# app1.net
KiCad netlist of a schematic drawn in EAGLE
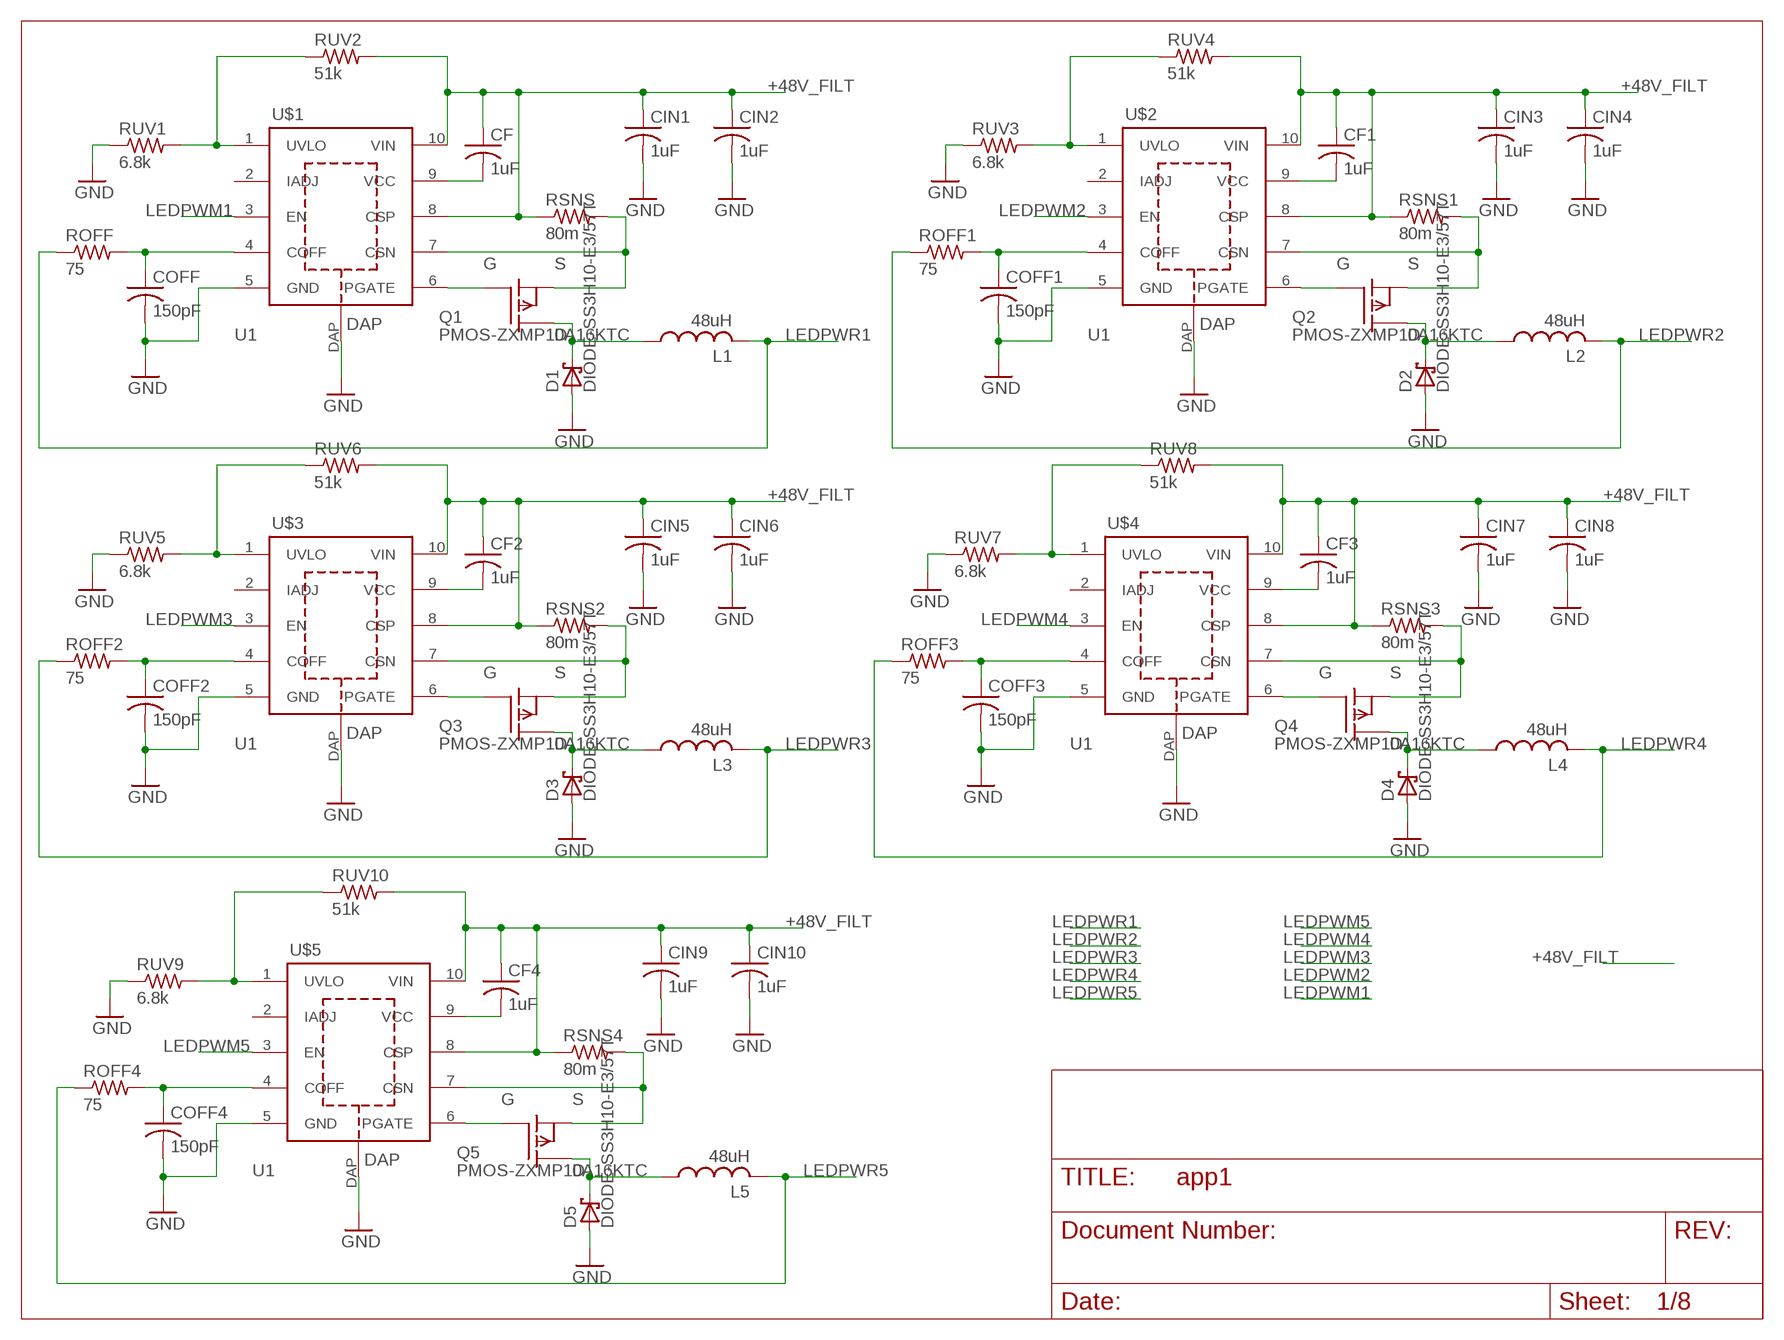
[diagram p0: schematic, sheet 1]
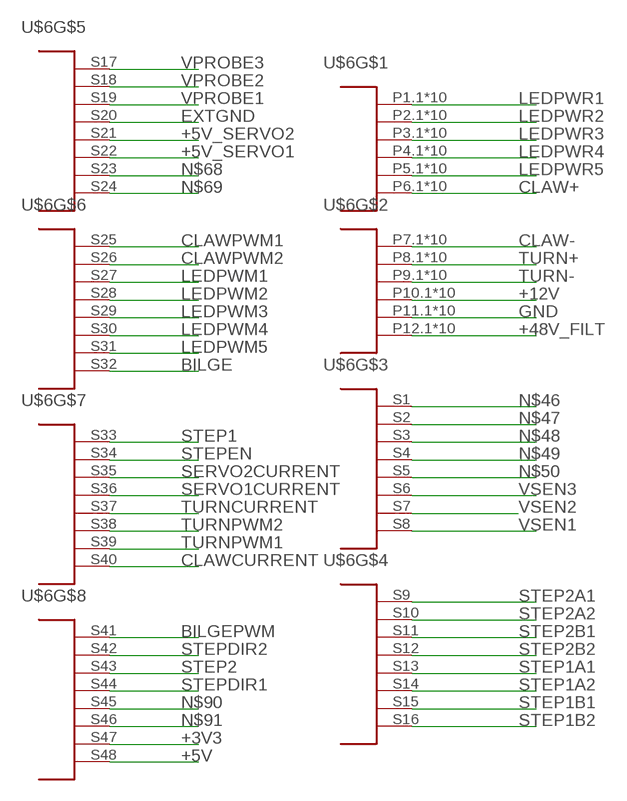
[diagram p1: schematic, sheet 2]
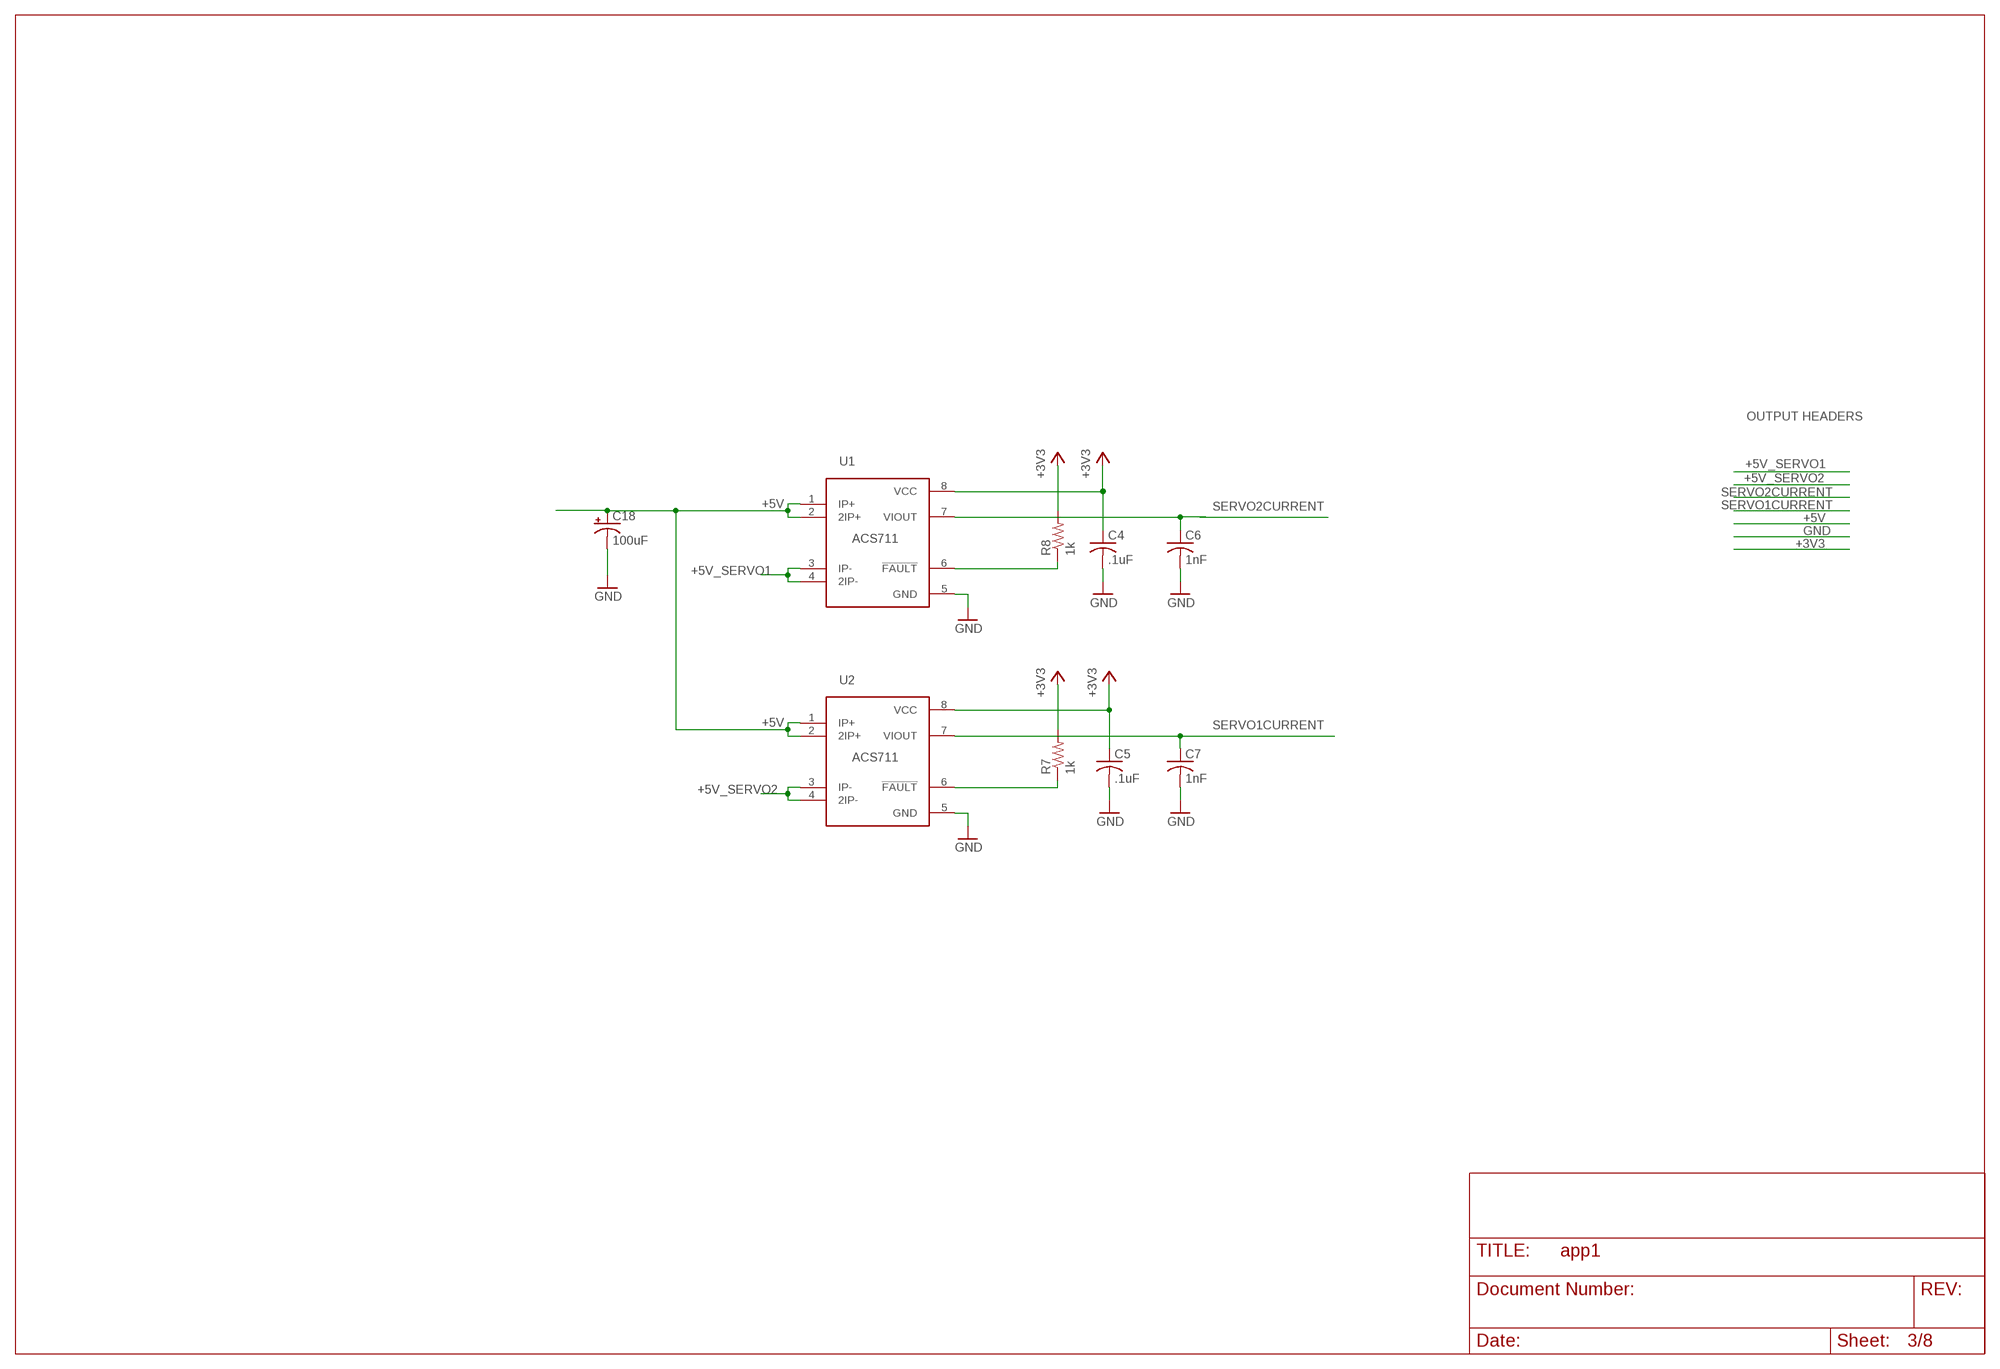
[diagram p2: schematic, sheet 3]
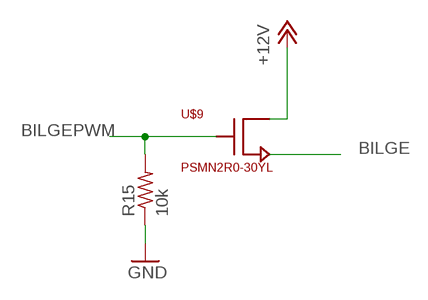
[diagram p3: schematic, sheet 4]
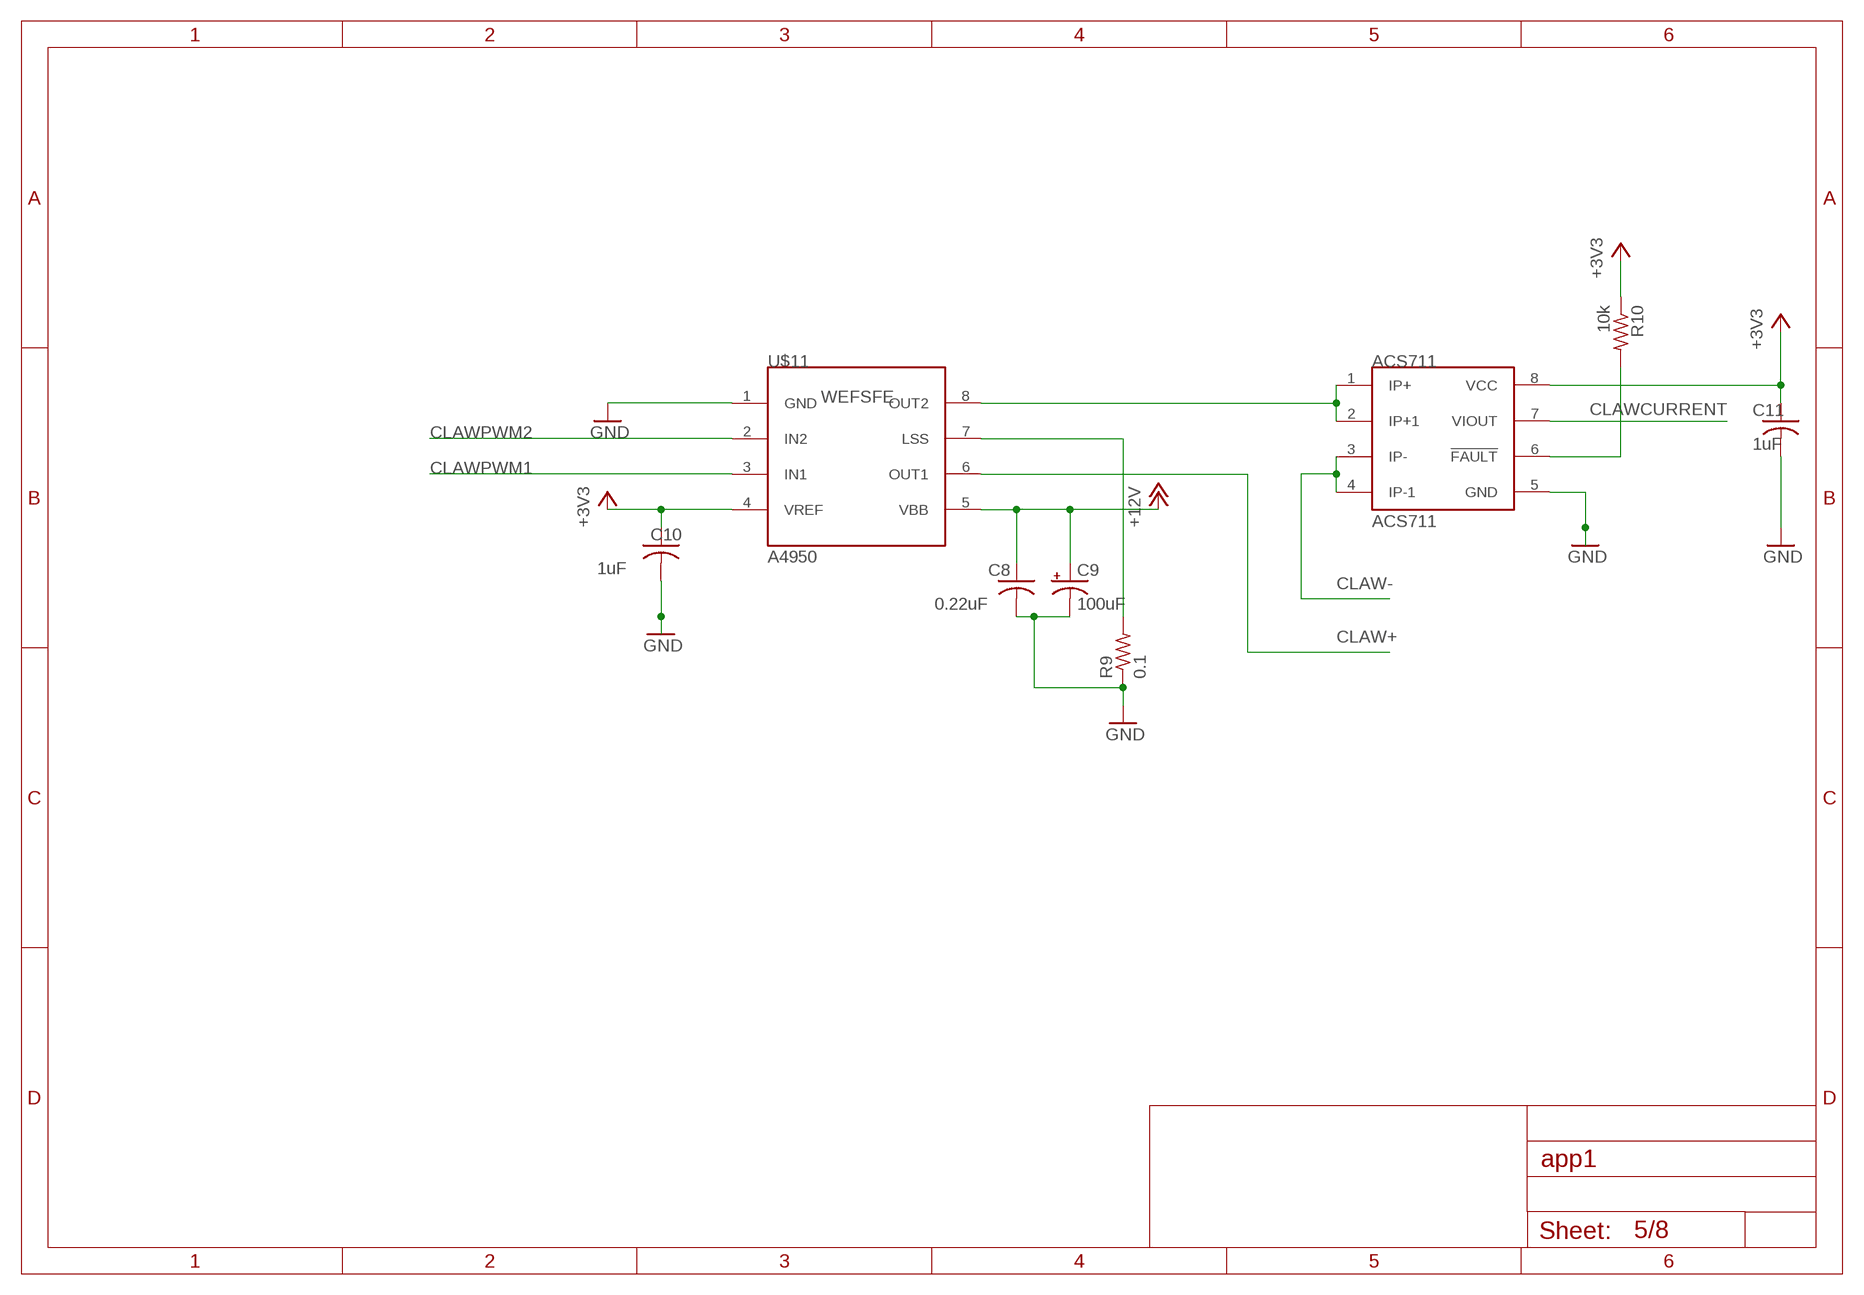
[diagram p4: schematic, sheet 5]
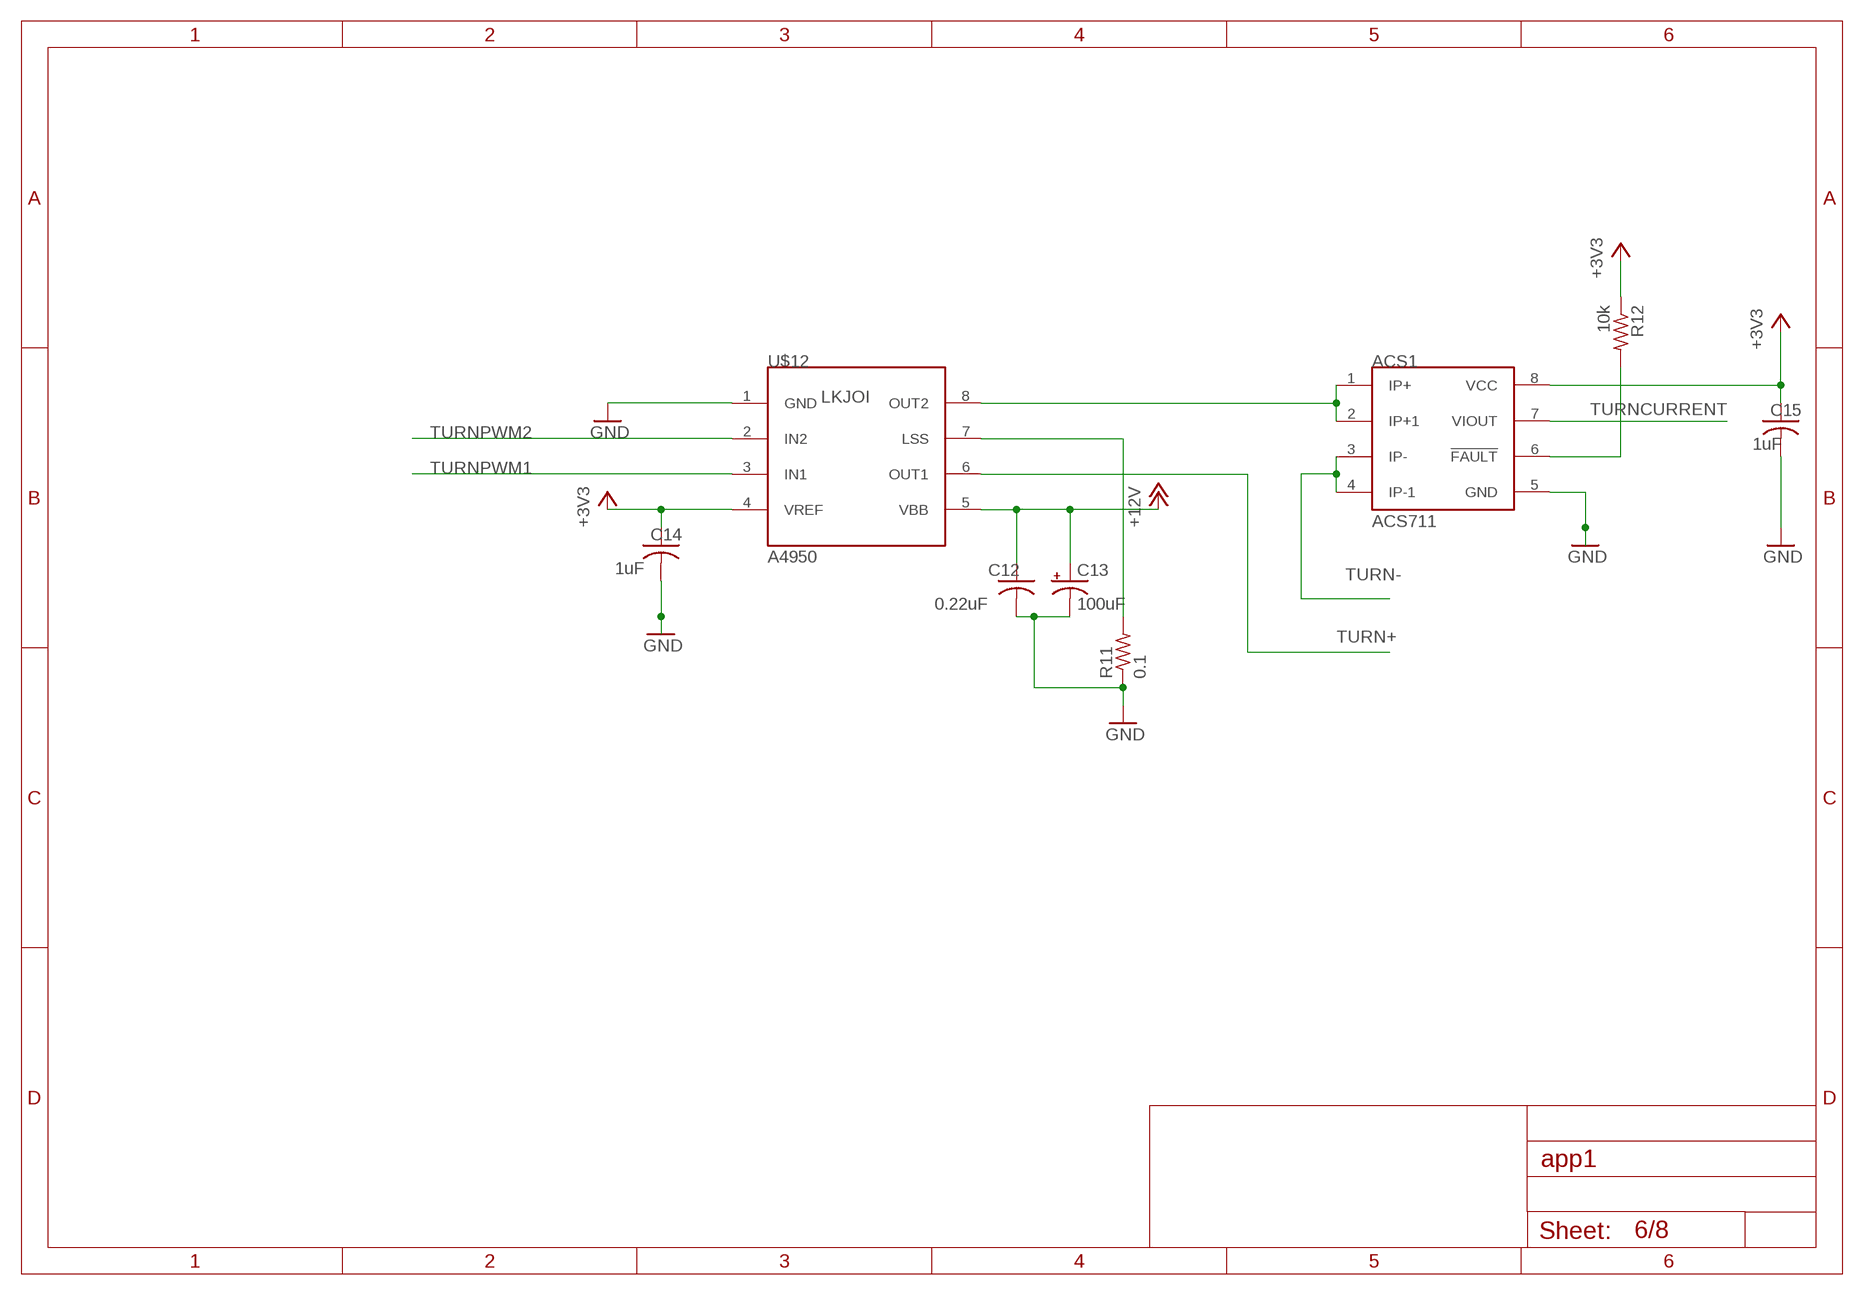
[diagram p5: schematic, sheet 6]
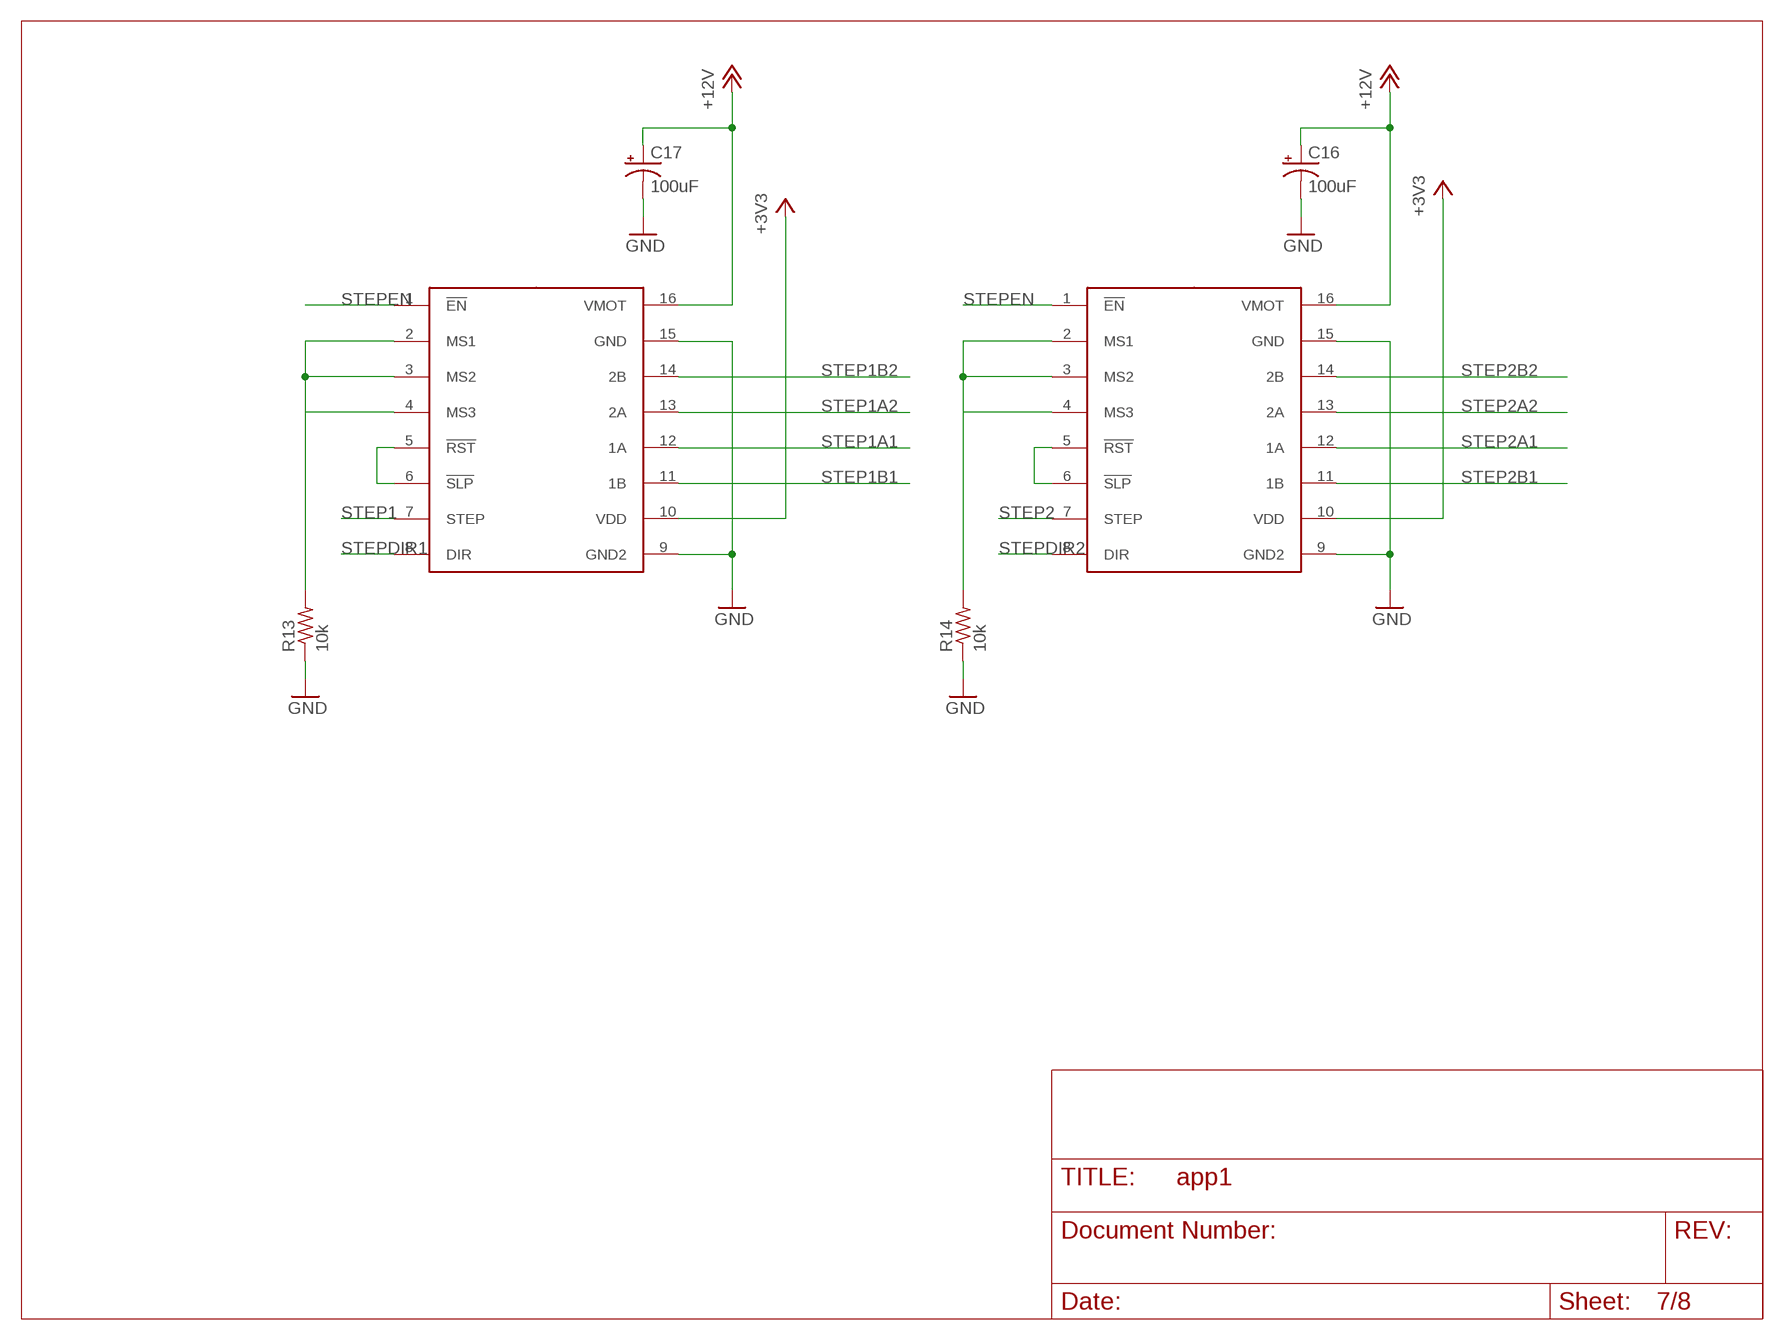
[diagram p6: schematic, sheet 7]
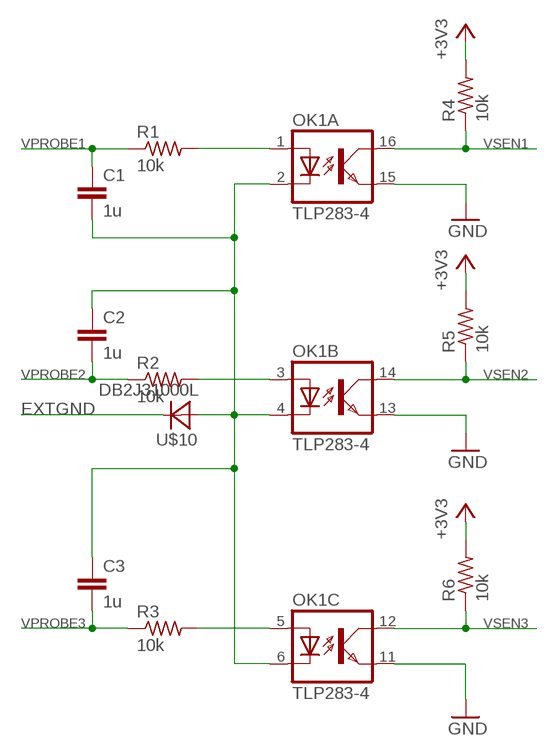
[diagram p7: schematic, sheet 8]

(export (version "E")
  (design (tool "Eeschema 10.0.6"))
  (components
    (comp (ref "ACS711")
      (value "ACS711")
      (footprint "eagle-import:SOIC8")
      (libsource (lib "eagle-import") (part "ACS711_ACS711"))
    )
    (comp (ref "C8")
      (value "0.22uF")
      (footprint "eagle-import:C0603")
      (libsource (lib "eagle-import") (part "C-USC0603"))
    )
    (comp (ref "C9")
      (value "100uF")
      (footprint "eagle-import:SANYO-OSCON_SMD_B6")
      (libsource (lib "eagle-import") (part "CPOL-USSANYO_SMD_B6"))
    )
    (comp (ref "C10")
      (value "1uF")
      (footprint "eagle-import:C0603")
      (libsource (lib "eagle-import") (part "C-USC0603"))
    )
    (comp (ref "C11")
      (value "1uF")
      (footprint "eagle-import:C0603")
      (libsource (lib "eagle-import") (part "C-USC0603"))
    )
    (comp (ref "R9")
      (value "0.1")
      (footprint "eagle-import:R0603")
      (libsource (lib "eagle-import") (part "R-US_R0603"))
    )
    (comp (ref "R10")
      (value "10k")
      (footprint "eagle-import:R0603")
      (libsource (lib "eagle-import") (part "R-US_R0603"))
    )
    (comp (ref "U$11")
      (value "A4950")
      (footprint "eagle-import:SOIC8-PAD")
      (libsource (lib "eagle-import") (part "A4950"))
    )
    (comp (ref "R15")
      (value "10k")
      (footprint "eagle-import:R0603")
      (libsource (lib "eagle-import") (part "R-US_R0603"))
    )
    (comp (ref "U$9")
      (value "PSMN2R0-30YL")
      (footprint "eagle-import:SOT669")
      (libsource (lib "eagle-import") (part "PSMN2R0-30YL"))
    )
    (comp (ref "C16")
      (value "100uF")
      (footprint "eagle-import:SANYO-OSCON_SMD_B6")
      (libsource (lib "eagle-import") (part "CPOL-USSANYO_SMD_B6"))
    )
    (comp (ref "C17")
      (value "100uF")
      (footprint "eagle-import:SANYO-OSCON_SMD_B6")
      (libsource (lib "eagle-import") (part "CPOL-USSANYO_SMD_B6"))
    )
    (comp (ref "R13")
      (value "10k")
      (footprint "eagle-import:R0603")
      (libsource (lib "eagle-import") (part "resistor_R-US_R0603"))
    )
    (comp (ref "R14")
      (value "10k")
      (footprint "eagle-import:R0603")
      (libsource (lib "eagle-import") (part "resistor_R-US_R0603"))
    )
    (comp (ref "U$7")
      (value "A4988")
      (footprint "eagle-import:FE08-2-0.6")
      (libsource (lib "eagle-import") (part "A4988"))
    )
    (comp (ref "U$8")
      (value "A4988")
      (footprint "eagle-import:FE08-2-0.6")
      (libsource (lib "eagle-import") (part "A4988"))
    )
    (comp (ref "C1")
      (value "1u")
      (footprint "eagle-import:C0603")
      (libsource (lib "eagle-import") (part "C-EUC0603"))
    )
    (comp (ref "C2")
      (value "1u")
      (footprint "eagle-import:C0603")
      (libsource (lib "eagle-import") (part "C-EUC0603"))
    )
    (comp (ref "C3")
      (value "1u")
      (footprint "eagle-import:C0603")
      (libsource (lib "eagle-import") (part "C-EUC0603"))
    )
    (comp (ref "OK1")
      (value "TLP283-4")
      (footprint "eagle-import:MINI-FLAT-16")
      (libsource (lib "eagle-import") (part "TLP283-4"))
    )
    (comp (ref "R1")
      (value "10k")
      (footprint "eagle-import:R0603")
      (libsource (lib "eagle-import") (part "R-US_R0603"))
    )
    (comp (ref "R2")
      (value "10k")
      (footprint "eagle-import:R0603")
      (libsource (lib "eagle-import") (part "R-US_R0603"))
    )
    (comp (ref "R3")
      (value "10k")
      (footprint "eagle-import:R0603")
      (libsource (lib "eagle-import") (part "R-US_R0603"))
    )
    (comp (ref "R4")
      (value "10k")
      (footprint "eagle-import:R0603")
      (libsource (lib "eagle-import") (part "R-US_R0603"))
    )
    (comp (ref "R5")
      (value "10k")
      (footprint "eagle-import:R0603")
      (libsource (lib "eagle-import") (part "R-US_R0603"))
    )
    (comp (ref "R6")
      (value "10k")
      (footprint "eagle-import:R0603")
      (libsource (lib "eagle-import") (part "R-US_R0603"))
    )
    (comp (ref "U$10")
      (value "DB2J31000L")
      (footprint "eagle-import:SOD323-R")
      (libsource (lib "eagle-import") (part "DB2J31000L"))
    )
    (comp (ref "C4")
      (value ".1uF")
      (footprint "eagle-import:C0603")
      (libsource (lib "eagle-import") (part "resistor_C-USC0603"))
    )
    (comp (ref "C5")
      (value ".1uF")
      (footprint "eagle-import:C0603")
      (libsource (lib "eagle-import") (part "resistor_C-USC0603"))
    )
    (comp (ref "C6")
      (value "1nF")
      (footprint "eagle-import:C0603K")
      (libsource (lib "eagle-import") (part "resistor_C-USC0603K"))
    )
    (comp (ref "C7")
      (value "1nF")
      (footprint "eagle-import:C0603K")
      (libsource (lib "eagle-import") (part "resistor_C-USC0603K"))
    )
    (comp (ref "C18")
      (value "100uF")
      (footprint "eagle-import:SANYO-OSCON_SMD_B6")
      (libsource (lib "eagle-import") (part "CPOL-USSANYO_SMD_B6"))
    )
    (comp (ref "R7")
      (value "1k")
      (footprint "eagle-import:R0603")
      (libsource (lib "eagle-import") (part "resistor_R-US_R0603"))
    )
    (comp (ref "R8")
      (value "1k")
      (footprint "eagle-import:R0603")
      (libsource (lib "eagle-import") (part "resistor_R-US_R0603"))
    )
    (comp (ref "U1")
      (value "ACS711")
      (footprint "eagle-import:8SOIC")
      (libsource (lib "eagle-import") (part "ACS711"))
    )
    (comp (ref "U2")
      (value "ACS711")
      (footprint "eagle-import:8SOIC")
      (libsource (lib "eagle-import") (part "ACS711"))
    )
    (comp (ref "U$6")
      (value "TEN60-P6-S24-S24-P6-RA")
      (footprint "eagle-import:TEN60-P6-S24-S24-P6-RA")
      (libsource (lib "eagle-import") (part "TEN60-P6-S24-S24-P6-RA"))
    )
    (comp (ref "CF")
      (value "1uF")
      (footprint "eagle-import:C0603")
      (libsource (lib "eagle-import") (part "C-USC0603"))
    )
    (comp (ref "CF1")
      (value "1uF")
      (footprint "eagle-import:C0603")
      (libsource (lib "eagle-import") (part "C-USC0603"))
    )
    (comp (ref "CF2")
      (value "1uF")
      (footprint "eagle-import:C0603")
      (libsource (lib "eagle-import") (part "C-USC0603"))
    )
    (comp (ref "CF3")
      (value "1uF")
      (footprint "eagle-import:C0603")
      (libsource (lib "eagle-import") (part "C-USC0603"))
    )
    (comp (ref "CF4")
      (value "1uF")
      (footprint "eagle-import:C0603")
      (libsource (lib "eagle-import") (part "C-USC0603"))
    )
    (comp (ref "CIN1")
      (value "1uF")
      (footprint "eagle-import:C1206")
      (libsource (lib "eagle-import") (part "C-USC1206"))
    )
    (comp (ref "CIN2")
      (value "1uF")
      (footprint "eagle-import:C1206")
      (libsource (lib "eagle-import") (part "C-USC1206"))
    )
    (comp (ref "CIN3")
      (value "1uF")
      (footprint "eagle-import:C1206")
      (libsource (lib "eagle-import") (part "C-USC1206"))
    )
    (comp (ref "CIN4")
      (value "1uF")
      (footprint "eagle-import:C1206")
      (libsource (lib "eagle-import") (part "C-USC1206"))
    )
    (comp (ref "CIN5")
      (value "1uF")
      (footprint "eagle-import:C1206")
      (libsource (lib "eagle-import") (part "C-USC1206"))
    )
    (comp (ref "CIN6")
      (value "1uF")
      (footprint "eagle-import:C1206")
      (libsource (lib "eagle-import") (part "C-USC1206"))
    )
    (comp (ref "CIN7")
      (value "1uF")
      (footprint "eagle-import:C1206")
      (libsource (lib "eagle-import") (part "C-USC1206"))
    )
    (comp (ref "CIN8")
      (value "1uF")
      (footprint "eagle-import:C1206")
      (libsource (lib "eagle-import") (part "C-USC1206"))
    )
    (comp (ref "CIN9")
      (value "1uF")
      (footprint "eagle-import:C1206")
      (libsource (lib "eagle-import") (part "C-USC1206"))
    )
    (comp (ref "CIN10")
      (value "1uF")
      (footprint "eagle-import:C1206")
      (libsource (lib "eagle-import") (part "C-USC1206"))
    )
    (comp (ref "COFF")
      (value "150pF")
      (footprint "eagle-import:C0603")
      (libsource (lib "eagle-import") (part "C-USC0603"))
    )
    (comp (ref "COFF1")
      (value "150pF")
      (footprint "eagle-import:C0603")
      (libsource (lib "eagle-import") (part "C-USC0603"))
    )
    (comp (ref "COFF2")
      (value "150pF")
      (footprint "eagle-import:C0603")
      (libsource (lib "eagle-import") (part "C-USC0603"))
    )
    (comp (ref "COFF3")
      (value "150pF")
      (footprint "eagle-import:C0603")
      (libsource (lib "eagle-import") (part "C-USC0603"))
    )
    (comp (ref "COFF4")
      (value "150pF")
      (footprint "eagle-import:C0603")
      (libsource (lib "eagle-import") (part "C-USC0603"))
    )
    (comp (ref "D1")
      (value "DIODE-SS3H10-E3/57T")
      (footprint "eagle-import:SMC")
      (libsource (lib "eagle-import") (part "DIODE-SS3H10-E3/9AT"))
    )
    (comp (ref "D2")
      (value "DIODE-SS3H10-E3/57T")
      (footprint "eagle-import:SMC")
      (libsource (lib "eagle-import") (part "DIODE-SS3H10-E3/9AT"))
    )
    (comp (ref "D3")
      (value "DIODE-SS3H10-E3/57T")
      (footprint "eagle-import:SMC")
      (libsource (lib "eagle-import") (part "DIODE-SS3H10-E3/9AT"))
    )
    (comp (ref "D4")
      (value "DIODE-SS3H10-E3/57T")
      (footprint "eagle-import:SMC")
      (libsource (lib "eagle-import") (part "DIODE-SS3H10-E3/9AT"))
    )
    (comp (ref "D5")
      (value "DIODE-SS3H10-E3/57T")
      (footprint "eagle-import:SMC")
      (libsource (lib "eagle-import") (part "DIODE-SS3H10-E3/9AT"))
    )
    (comp (ref "L1")
      (value "48uH")
      (footprint "eagle-import:SRP1265A")
      (libsource (lib "eagle-import") (part "SRP1265A"))
    )
    (comp (ref "L2")
      (value "48uH")
      (footprint "eagle-import:SRP1265A")
      (libsource (lib "eagle-import") (part "SRP1265A"))
    )
    (comp (ref "L3")
      (value "48uH")
      (footprint "eagle-import:SRP1265A")
      (libsource (lib "eagle-import") (part "SRP1265A"))
    )
    (comp (ref "L4")
      (value "48uH")
      (footprint "eagle-import:SRP1265A")
      (libsource (lib "eagle-import") (part "SRP1265A"))
    )
    (comp (ref "L5")
      (value "48uH")
      (footprint "eagle-import:SRP1265A")
      (libsource (lib "eagle-import") (part "SRP1265A"))
    )
    (comp (ref "Q1")
      (value "PMOS-ZXMP10A16KTC")
      (footprint "eagle-import:TO252")
      (libsource (lib "eagle-import") (part "PMOS-ZXMP10A18KTC"))
    )
    (comp (ref "Q2")
      (value "PMOS-ZXMP10A16KTC")
      (footprint "eagle-import:TO252")
      (libsource (lib "eagle-import") (part "PMOS-ZXMP10A18KTC"))
    )
    (comp (ref "Q3")
      (value "PMOS-ZXMP10A16KTC")
      (footprint "eagle-import:TO252")
      (libsource (lib "eagle-import") (part "PMOS-ZXMP10A18KTC"))
    )
    (comp (ref "Q4")
      (value "PMOS-ZXMP10A16KTC")
      (footprint "eagle-import:TO252")
      (libsource (lib "eagle-import") (part "PMOS-ZXMP10A18KTC"))
    )
    (comp (ref "Q5")
      (value "PMOS-ZXMP10A16KTC")
      (footprint "eagle-import:TO252")
      (libsource (lib "eagle-import") (part "PMOS-ZXMP10A18KTC"))
    )
    (comp (ref "ROFF")
      (value "75")
      (footprint "eagle-import:R0603")
      (libsource (lib "eagle-import") (part "R-US_R0603"))
    )
    (comp (ref "ROFF1")
      (value "75")
      (footprint "eagle-import:R0603")
      (libsource (lib "eagle-import") (part "R-US_R0603"))
    )
    (comp (ref "ROFF2")
      (value "75")
      (footprint "eagle-import:R0603")
      (libsource (lib "eagle-import") (part "R-US_R0603"))
    )
    (comp (ref "ROFF3")
      (value "75")
      (footprint "eagle-import:R0603")
      (libsource (lib "eagle-import") (part "R-US_R0603"))
    )
    (comp (ref "ROFF4")
      (value "75")
      (footprint "eagle-import:R0603")
      (libsource (lib "eagle-import") (part "R-US_R0603"))
    )
    (comp (ref "RSNS")
      (value "80m")
      (footprint "eagle-import:R2512")
      (libsource (lib "eagle-import") (part "R-US_R2512"))
    )
    (comp (ref "RSNS1")
      (value "80m")
      (footprint "eagle-import:R2512")
      (libsource (lib "eagle-import") (part "R-US_R2512"))
    )
    (comp (ref "RSNS2")
      (value "80m")
      (footprint "eagle-import:R2512")
      (libsource (lib "eagle-import") (part "R-US_R2512"))
    )
    (comp (ref "RSNS3")
      (value "80m")
      (footprint "eagle-import:R2512")
      (libsource (lib "eagle-import") (part "R-US_R2512"))
    )
    (comp (ref "RSNS4")
      (value "80m")
      (footprint "eagle-import:R2512")
      (libsource (lib "eagle-import") (part "R-US_R2512"))
    )
    (comp (ref "RUV1")
      (value "6.8k")
      (footprint "eagle-import:R0603")
      (libsource (lib "eagle-import") (part "R-US_R0603"))
    )
    (comp (ref "RUV2")
      (value "51k")
      (footprint "eagle-import:R0603")
      (libsource (lib "eagle-import") (part "R-US_R0603"))
    )
    (comp (ref "RUV3")
      (value "6.8k")
      (footprint "eagle-import:R0603")
      (libsource (lib "eagle-import") (part "R-US_R0603"))
    )
    (comp (ref "RUV4")
      (value "51k")
      (footprint "eagle-import:R0603")
      (libsource (lib "eagle-import") (part "R-US_R0603"))
    )
    (comp (ref "RUV5")
      (value "6.8k")
      (footprint "eagle-import:R0603")
      (libsource (lib "eagle-import") (part "R-US_R0603"))
    )
    (comp (ref "RUV6")
      (value "51k")
      (footprint "eagle-import:R0603")
      (libsource (lib "eagle-import") (part "R-US_R0603"))
    )
    (comp (ref "RUV7")
      (value "6.8k")
      (footprint "eagle-import:R0603")
      (libsource (lib "eagle-import") (part "R-US_R0603"))
    )
    (comp (ref "RUV8")
      (value "51k")
      (footprint "eagle-import:R0603")
      (libsource (lib "eagle-import") (part "R-US_R0603"))
    )
    (comp (ref "RUV9")
      (value "6.8k")
      (footprint "eagle-import:R0603")
      (libsource (lib "eagle-import") (part "R-US_R0603"))
    )
    (comp (ref "RUV10")
      (value "51k")
      (footprint "eagle-import:R0603")
      (libsource (lib "eagle-import") (part "R-US_R0603"))
    )
    (comp (ref "U$1")
      (value "U1")
      (footprint "eagle-import:VSSOP-10")
      (libsource (lib "eagle-import") (part "LM3409HV'LM3409HV'"))
    )
    (comp (ref "U$2")
      (value "U1")
      (footprint "eagle-import:VSSOP-10")
      (libsource (lib "eagle-import") (part "LM3409HV'LM3409HV'"))
    )
    (comp (ref "U$3")
      (value "U1")
      (footprint "eagle-import:VSSOP-10")
      (libsource (lib "eagle-import") (part "LM3409HV'LM3409HV'"))
    )
    (comp (ref "U$4")
      (value "U1")
      (footprint "eagle-import:VSSOP-10")
      (libsource (lib "eagle-import") (part "LM3409HV'LM3409HV'"))
    )
    (comp (ref "U$5")
      (value "U1")
      (footprint "eagle-import:VSSOP-10")
      (libsource (lib "eagle-import") (part "LM3409HV'LM3409HV'"))
    )
    (comp (ref "ACS1")
      (value "ACS711")
      (footprint "eagle-import:SOIC8")
      (libsource (lib "eagle-import") (part "ACS711_ACS711"))
    )
    (comp (ref "C12")
      (value "0.22uF")
      (footprint "eagle-import:C0603")
      (libsource (lib "eagle-import") (part "C-USC0603"))
    )
    (comp (ref "C13")
      (value "100uF")
      (footprint "eagle-import:SANYO-OSCON_SMD_B6")
      (libsource (lib "eagle-import") (part "CPOL-USSANYO_SMD_B6"))
    )
    (comp (ref "C14")
      (value "1uF")
      (footprint "eagle-import:C0603")
      (libsource (lib "eagle-import") (part "C-USC0603"))
    )
    (comp (ref "C15")
      (value "1uF")
      (footprint "eagle-import:C0603")
      (libsource (lib "eagle-import") (part "C-USC0603"))
    )
    (comp (ref "R11")
      (value "0.1")
      (footprint "eagle-import:R0603")
      (libsource (lib "eagle-import") (part "R-US_R0603"))
    )
    (comp (ref "R12")
      (value "10k")
      (footprint "eagle-import:R0603")
      (libsource (lib "eagle-import") (part "R-US_R0603"))
    )
    (comp (ref "U$12")
      (value "A4950")
      (footprint "eagle-import:SOIC8-PAD")
      (libsource (lib "eagle-import") (part "A4950"))
    )
  )
  (nets
    (net (code "1") (name "+3V3") (class "Default")
      (node (ref "ACS1") (pin "8") (pinfunction "VCC_8") (pintype "bidirectional"))
      (node (ref "ACS711") (pin "8") (pinfunction "VCC_8") (pintype "bidirectional"))
      (node (ref "C10") (pin "1") (pinfunction "1_1") (pintype "passive"))
      (node (ref "C11") (pin "1") (pinfunction "1_1") (pintype "passive"))
      (node (ref "C14") (pin "1") (pinfunction "1_1") (pintype "passive"))
      (node (ref "C15") (pin "1") (pinfunction "1_1") (pintype "passive"))
      (node (ref "C4") (pin "1") (pinfunction "1_1") (pintype "passive"))
      (node (ref "C5") (pin "1") (pinfunction "1_1") (pintype "passive"))
      (node (ref "R10") (pin "1") (pinfunction "1_1") (pintype "passive"))
      (node (ref "R12") (pin "1") (pinfunction "1_1") (pintype "passive"))
      (node (ref "R4") (pin "2") (pinfunction "2_2") (pintype "passive"))
      (node (ref "R5") (pin "2") (pinfunction "2_2") (pintype "passive"))
      (node (ref "R6") (pin "2") (pinfunction "2_2") (pintype "passive"))
      (node (ref "R7") (pin "2") (pinfunction "2_2") (pintype "passive"))
      (node (ref "R8") (pin "2") (pinfunction "2_2") (pintype "passive"))
      (node (ref "U$11") (pin "4") (pinfunction "VREF_4") (pintype "bidirectional"))
      (node (ref "U$12") (pin "4") (pinfunction "VREF_4") (pintype "bidirectional"))
      (node (ref "U$6") (pin "S47") (pinfunction "P$7_S47") (pintype "bidirectional"))
      (node (ref "U$7") (pin "10") (pinfunction "VDD_10") (pintype "bidirectional"))
      (node (ref "U$8") (pin "10") (pinfunction "VDD_10") (pintype "bidirectional"))
      (node (ref "U1") (pin "8") (pinfunction "VCC_8") (pintype "bidirectional"))
      (node (ref "U2") (pin "8") (pinfunction "VCC_8") (pintype "bidirectional"))
    )
    (net (code "2") (name "+5V") (class "Default")
      (node (ref "C18") (pin "+") (pinfunction "+_+") (pintype "passive"))
      (node (ref "U$6") (pin "S48") (pinfunction "P$8_S48") (pintype "bidirectional"))
      (node (ref "U1") (pin "1") (pinfunction "IP+_1") (pintype "bidirectional"))
      (node (ref "U1") (pin "2") (pinfunction "2IP+_2") (pintype "bidirectional"))
      (node (ref "U2") (pin "1") (pinfunction "IP+_1") (pintype "bidirectional"))
      (node (ref "U2") (pin "2") (pinfunction "2IP+_2") (pintype "bidirectional"))
    )
    (net (code "3") (name "+5V_SERVO1") (class "Default")
      (node (ref "U$6") (pin "S22") (pinfunction "P$6_S22") (pintype "bidirectional"))
      (node (ref "U1") (pin "3") (pinfunction "IP-_3") (pintype "bidirectional"))
      (node (ref "U1") (pin "4") (pinfunction "2IP-_4") (pintype "bidirectional"))
    )
    (net (code "4") (name "+5V_SERVO2") (class "Default")
      (node (ref "U$6") (pin "S21") (pinfunction "P$5_S21") (pintype "bidirectional"))
      (node (ref "U2") (pin "3") (pinfunction "IP-_3") (pintype "bidirectional"))
      (node (ref "U2") (pin "4") (pinfunction "2IP-_4") (pintype "bidirectional"))
    )
    (net (code "5") (name "+12V") (class "Default")
      (node (ref "C12") (pin "1") (pinfunction "1_1") (pintype "passive"))
      (node (ref "C13") (pin "+") (pinfunction "+_+") (pintype "passive"))
      (node (ref "C16") (pin "+") (pinfunction "+_+") (pintype "passive"))
      (node (ref "C17") (pin "+") (pinfunction "+_+") (pintype "passive"))
      (node (ref "C8") (pin "1") (pinfunction "1_1") (pintype "passive"))
      (node (ref "C9") (pin "+") (pinfunction "+_+") (pintype "passive"))
      (node (ref "U$11") (pin "5") (pinfunction "VBB_5") (pintype "bidirectional"))
      (node (ref "U$12") (pin "5") (pinfunction "VBB_5") (pintype "bidirectional"))
      (node (ref "U$6") (pin "P10.1") (pinfunction "P$4_P10.1") (pintype "bidirectional"))
      (node (ref "U$6") (pin "P10.10") (pinfunction "P$4_P10.10") (pintype "bidirectional"))
      (node (ref "U$6") (pin "P10.2") (pinfunction "P$4_P10.2") (pintype "bidirectional"))
      (node (ref "U$6") (pin "P10.3") (pinfunction "P$4_P10.3") (pintype "bidirectional"))
      (node (ref "U$6") (pin "P10.4") (pinfunction "P$4_P10.4") (pintype "bidirectional"))
      (node (ref "U$6") (pin "P10.5") (pinfunction "P$4_P10.5") (pintype "bidirectional"))
      (node (ref "U$6") (pin "P10.6") (pinfunction "P$4_P10.6") (pintype "bidirectional"))
      (node (ref "U$6") (pin "P10.7") (pinfunction "P$4_P10.7") (pintype "bidirectional"))
      (node (ref "U$6") (pin "P10.8") (pinfunction "P$4_P10.8") (pintype "bidirectional"))
      (node (ref "U$6") (pin "P10.9") (pinfunction "P$4_P10.9") (pintype "bidirectional"))
      (node (ref "U$7") (pin "16") (pinfunction "VMOT_16") (pintype "bidirectional"))
      (node (ref "U$8") (pin "16") (pinfunction "VMOT_16") (pintype "bidirectional"))
      (node (ref "U$9") (pin "MB") (pinfunction "DRAIN_MB") (pintype "bidirectional"))
    )
    (net (code "6") (name "+48V_FILT") (class "Default")
      (node (ref "CF") (pin "1") (pinfunction "1_1") (pintype "passive"))
      (node (ref "CF1") (pin "1") (pinfunction "1_1") (pintype "passive"))
      (node (ref "CF2") (pin "1") (pinfunction "1_1") (pintype "passive"))
      (node (ref "CF3") (pin "1") (pinfunction "1_1") (pintype "passive"))
      (node (ref "CF4") (pin "1") (pinfunction "1_1") (pintype "passive"))
      (node (ref "CIN1") (pin "1") (pinfunction "1_1") (pintype "passive"))
      (node (ref "CIN10") (pin "1") (pinfunction "1_1") (pintype "passive"))
      (node (ref "CIN2") (pin "1") (pinfunction "1_1") (pintype "passive"))
      (node (ref "CIN3") (pin "1") (pinfunction "1_1") (pintype "passive"))
      (node (ref "CIN4") (pin "1") (pinfunction "1_1") (pintype "passive"))
      (node (ref "CIN5") (pin "1") (pinfunction "1_1") (pintype "passive"))
      (node (ref "CIN6") (pin "1") (pinfunction "1_1") (pintype "passive"))
      (node (ref "CIN7") (pin "1") (pinfunction "1_1") (pintype "passive"))
      (node (ref "CIN8") (pin "1") (pinfunction "1_1") (pintype "passive"))
      (node (ref "CIN9") (pin "1") (pinfunction "1_1") (pintype "passive"))
      (node (ref "RSNS") (pin "1") (pinfunction "1_1") (pintype "passive"))
      (node (ref "RSNS1") (pin "1") (pinfunction "1_1") (pintype "passive"))
      (node (ref "RSNS2") (pin "1") (pinfunction "1_1") (pintype "passive"))
      (node (ref "RSNS3") (pin "1") (pinfunction "1_1") (pintype "passive"))
      (node (ref "RSNS4") (pin "1") (pinfunction "1_1") (pintype "passive"))
      (node (ref "RUV10") (pin "2") (pinfunction "2_2") (pintype "passive"))
      (node (ref "RUV2") (pin "2") (pinfunction "2_2") (pintype "passive"))
      (node (ref "RUV4") (pin "2") (pinfunction "2_2") (pintype "passive"))
      (node (ref "RUV6") (pin "2") (pinfunction "2_2") (pintype "passive"))
      (node (ref "RUV8") (pin "2") (pinfunction "2_2") (pintype "passive"))
      (node (ref "U$1") (pin "10") (pinfunction "VIN_10") (pintype "bidirectional"))
      (node (ref "U$1") (pin "8") (pinfunction "CSP_8") (pintype "bidirectional"))
      (node (ref "U$2") (pin "10") (pinfunction "VIN_10") (pintype "bidirectional"))
      (node (ref "U$2") (pin "8") (pinfunction "CSP_8") (pintype "bidirectional"))
      (node (ref "U$3") (pin "10") (pinfunction "VIN_10") (pintype "bidirectional"))
      (node (ref "U$3") (pin "8") (pinfunction "CSP_8") (pintype "bidirectional"))
      (node (ref "U$4") (pin "10") (pinfunction "VIN_10") (pintype "bidirectional"))
      (node (ref "U$4") (pin "8") (pinfunction "CSP_8") (pintype "bidirectional"))
      (node (ref "U$5") (pin "10") (pinfunction "VIN_10") (pintype "bidirectional"))
      (node (ref "U$5") (pin "8") (pinfunction "CSP_8") (pintype "bidirectional"))
      (node (ref "U$6") (pin "P12.1") (pinfunction "P$6_P12.1") (pintype "bidirectional"))
      (node (ref "U$6") (pin "P12.10") (pinfunction "P$6_P12.10") (pintype "bidirectional"))
      (node (ref "U$6") (pin "P12.2") (pinfunction "P$6_P12.2") (pintype "bidirectional"))
      (node (ref "U$6") (pin "P12.3") (pinfunction "P$6_P12.3") (pintype "bidirectional"))
      (node (ref "U$6") (pin "P12.4") (pinfunction "P$6_P12.4") (pintype "bidirectional"))
      (node (ref "U$6") (pin "P12.5") (pinfunction "P$6_P12.5") (pintype "bidirectional"))
      (node (ref "U$6") (pin "P12.6") (pinfunction "P$6_P12.6") (pintype "bidirectional"))
      (node (ref "U$6") (pin "P12.7") (pinfunction "P$6_P12.7") (pintype "bidirectional"))
      (node (ref "U$6") (pin "P12.8") (pinfunction "P$6_P12.8") (pintype "bidirectional"))
      (node (ref "U$6") (pin "P12.9") (pinfunction "P$6_P12.9") (pintype "bidirectional"))
    )
    (net (code "7") (name "BILGE") (class "Default")
      (node (ref "U$6") (pin "S32") (pinfunction "P$8_S32") (pintype "bidirectional"))
      (node (ref "U$9") (pin "1") (pinfunction "SOURCE_1") (pintype "bidirectional"))
      (node (ref "U$9") (pin "2") (pinfunction "SOURCE_2") (pintype "bidirectional"))
      (node (ref "U$9") (pin "3") (pinfunction "SOURCE_3") (pintype "bidirectional"))
    )
    (net (code "8") (name "BILGEPWM") (class "Default")
      (node (ref "R15") (pin "2") (pinfunction "2_2") (pintype "passive"))
      (node (ref "U$6") (pin "S41") (pinfunction "P$1_S41") (pintype "bidirectional"))
      (node (ref "U$9") (pin "4") (pinfunction "GATE_4") (pintype "bidirectional"))
    )
    (net (code "9") (name "CLAW+") (class "Default")
      (node (ref "U$11") (pin "6") (pinfunction "OUT1_6") (pintype "bidirectional"))
      (node (ref "U$6") (pin "P6.1") (pinfunction "P$6_P6.1") (pintype "bidirectional"))
      (node (ref "U$6") (pin "P6.10") (pinfunction "P$6_P6.10") (pintype "bidirectional"))
      (node (ref "U$6") (pin "P6.2") (pinfunction "P$6_P6.2") (pintype "bidirectional"))
      (node (ref "U$6") (pin "P6.3") (pinfunction "P$6_P6.3") (pintype "bidirectional"))
      (node (ref "U$6") (pin "P6.4") (pinfunction "P$6_P6.4") (pintype "bidirectional"))
      (node (ref "U$6") (pin "P6.5") (pinfunction "P$6_P6.5") (pintype "bidirectional"))
      (node (ref "U$6") (pin "P6.6") (pinfunction "P$6_P6.6") (pintype "bidirectional"))
      (node (ref "U$6") (pin "P6.7") (pinfunction "P$6_P6.7") (pintype "bidirectional"))
      (node (ref "U$6") (pin "P6.8") (pinfunction "P$6_P6.8") (pintype "bidirectional"))
      (node (ref "U$6") (pin "P6.9") (pinfunction "P$6_P6.9") (pintype "bidirectional"))
    )
    (net (code "10") (name "CLAW-") (class "Default")
      (node (ref "ACS711") (pin "3") (pinfunction "IP-_3") (pintype "bidirectional"))
      (node (ref "ACS711") (pin "4") (pinfunction "IP-1_4") (pintype "bidirectional"))
      (node (ref "U$6") (pin "P7.1") (pinfunction "P$1_P7.1") (pintype "bidirectional"))
      (node (ref "U$6") (pin "P7.10") (pinfunction "P$1_P7.10") (pintype "bidirectional"))
      (node (ref "U$6") (pin "P7.2") (pinfunction "P$1_P7.2") (pintype "bidirectional"))
      (node (ref "U$6") (pin "P7.3") (pinfunction "P$1_P7.3") (pintype "bidirectional"))
      (node (ref "U$6") (pin "P7.4") (pinfunction "P$1_P7.4") (pintype "bidirectional"))
      (node (ref "U$6") (pin "P7.5") (pinfunction "P$1_P7.5") (pintype "bidirectional"))
      (node (ref "U$6") (pin "P7.6") (pinfunction "P$1_P7.6") (pintype "bidirectional"))
      (node (ref "U$6") (pin "P7.7") (pinfunction "P$1_P7.7") (pintype "bidirectional"))
      (node (ref "U$6") (pin "P7.8") (pinfunction "P$1_P7.8") (pintype "bidirectional"))
      (node (ref "U$6") (pin "P7.9") (pinfunction "P$1_P7.9") (pintype "bidirectional"))
    )
    (net (code "11") (name "CLAWCURRENT") (class "Default")
      (node (ref "ACS711") (pin "7") (pinfunction "VIOUT_7") (pintype "bidirectional"))
      (node (ref "U$6") (pin "S40") (pinfunction "P$8_S40") (pintype "bidirectional"))
    )
    (net (code "12") (name "CLAWPWM1") (class "Default")
      (node (ref "U$11") (pin "3") (pinfunction "IN1_3") (pintype "bidirectional"))
      (node (ref "U$6") (pin "S25") (pinfunction "P$1_S25") (pintype "bidirectional"))
    )
    (net (code "13") (name "CLAWPWM2") (class "Default")
      (node (ref "U$11") (pin "2") (pinfunction "IN2_2") (pintype "bidirectional"))
      (node (ref "U$6") (pin "S26") (pinfunction "P$2_S26") (pintype "bidirectional"))
    )
    (net (code "14") (name "EXTGND") (class "Default")
      (node (ref "U$10") (pin "C") (pinfunction "C_C") (pintype "passive"))
      (node (ref "U$6") (pin "S20") (pinfunction "P$4_S20") (pintype "bidirectional"))
    )
    (net (code "15") (name "GND") (class "Default")
      (node (ref "ACS1") (pin "5") (pinfunction "GND_5") (pintype "bidirectional"))
      (node (ref "ACS711") (pin "5") (pinfunction "GND_5") (pintype "bidirectional"))
      (node (ref "C10") (pin "2") (pinfunction "2_2") (pintype "passive"))
      (node (ref "C11") (pin "2") (pinfunction "2_2") (pintype "passive"))
      (node (ref "C12") (pin "2") (pinfunction "2_2") (pintype "passive"))
      (node (ref "C13") (pin "-") (pinfunction "-_-") (pintype "passive"))
      (node (ref "C14") (pin "2") (pinfunction "2_2") (pintype "passive"))
      (node (ref "C15") (pin "2") (pinfunction "2_2") (pintype "passive"))
      (node (ref "C16") (pin "-") (pinfunction "-_-") (pintype "passive"))
      (node (ref "C17") (pin "-") (pinfunction "-_-") (pintype "passive"))
      (node (ref "C18") (pin "-") (pinfunction "-_-") (pintype "passive"))
      (node (ref "C4") (pin "2") (pinfunction "2_2") (pintype "passive"))
      (node (ref "C5") (pin "2") (pinfunction "2_2") (pintype "passive"))
      (node (ref "C6") (pin "2") (pinfunction "2_2") (pintype "passive"))
      (node (ref "C7") (pin "2") (pinfunction "2_2") (pintype "passive"))
      (node (ref "C8") (pin "2") (pinfunction "2_2") (pintype "passive"))
      (node (ref "C9") (pin "-") (pinfunction "-_-") (pintype "passive"))
      (node (ref "CIN1") (pin "2") (pinfunction "2_2") (pintype "passive"))
      (node (ref "CIN10") (pin "2") (pinfunction "2_2") (pintype "passive"))
      (node (ref "CIN2") (pin "2") (pinfunction "2_2") (pintype "passive"))
      (node (ref "CIN3") (pin "2") (pinfunction "2_2") (pintype "passive"))
      (node (ref "CIN4") (pin "2") (pinfunction "2_2") (pintype "passive"))
      (node (ref "CIN5") (pin "2") (pinfunction "2_2") (pintype "passive"))
      (node (ref "CIN6") (pin "2") (pinfunction "2_2") (pintype "passive"))
      (node (ref "CIN7") (pin "2") (pinfunction "2_2") (pintype "passive"))
      (node (ref "CIN8") (pin "2") (pinfunction "2_2") (pintype "passive"))
      (node (ref "CIN9") (pin "2") (pinfunction "2_2") (pintype "passive"))
      (node (ref "COFF") (pin "2") (pinfunction "2_2") (pintype "passive"))
      (node (ref "COFF1") (pin "2") (pinfunction "2_2") (pintype "passive"))
      (node (ref "COFF2") (pin "2") (pinfunction "2_2") (pintype "passive"))
      (node (ref "COFF3") (pin "2") (pinfunction "2_2") (pintype "passive"))
      (node (ref "COFF4") (pin "2") (pinfunction "2_2") (pintype "passive"))
      (node (ref "D1") (pin "A") (pinfunction "A_A") (pintype "passive"))
      (node (ref "D2") (pin "A") (pinfunction "A_A") (pintype "passive"))
      (node (ref "D3") (pin "A") (pinfunction "A_A") (pintype "passive"))
      (node (ref "D4") (pin "A") (pinfunction "A_A") (pintype "passive"))
      (node (ref "D5") (pin "A") (pinfunction "A_A") (pintype "passive"))
      (node (ref "OK1") (pin "11") (pinfunction "EMIT_11") (pintype "passive"))
      (node (ref "OK1") (pin "13") (pinfunction "EMIT_13") (pintype "passive"))
      (node (ref "OK1") (pin "15") (pinfunction "EMIT_15") (pintype "passive"))
      (node (ref "R11") (pin "1") (pinfunction "1_1") (pintype "passive"))
      (node (ref "R13") (pin "1") (pinfunction "1_1") (pintype "passive"))
      (node (ref "R14") (pin "1") (pinfunction "1_1") (pintype "passive"))
      (node (ref "R15") (pin "1") (pinfunction "1_1") (pintype "passive"))
      (node (ref "R9") (pin "1") (pinfunction "1_1") (pintype "passive"))
      (node (ref "RUV1") (pin "1") (pinfunction "1_1") (pintype "passive"))
      (node (ref "RUV3") (pin "1") (pinfunction "1_1") (pintype "passive"))
      (node (ref "RUV5") (pin "1") (pinfunction "1_1") (pintype "passive"))
      (node (ref "RUV7") (pin "1") (pinfunction "1_1") (pintype "passive"))
      (node (ref "RUV9") (pin "1") (pinfunction "1_1") (pintype "passive"))
      (node (ref "U$1") (pin "5") (pinfunction "GND_5") (pintype "bidirectional"))
      (node (ref "U$1") (pin "DAP") (pinfunction "DAP_DAP") (pintype "bidirectional"))
      (node (ref "U$11") (pin "1") (pinfunction "GND_1") (pintype "bidirectional"))
      (node (ref "U$12") (pin "1") (pinfunction "GND_1") (pintype "bidirectional"))
      (node (ref "U$2") (pin "5") (pinfunction "GND_5") (pintype "bidirectional"))
      (node (ref "U$2") (pin "DAP") (pinfunction "DAP_DAP") (pintype "bidirectional"))
      (node (ref "U$3") (pin "5") (pinfunction "GND_5") (pintype "bidirectional"))
      (node (ref "U$3") (pin "DAP") (pinfunction "DAP_DAP") (pintype "bidirectional"))
      (node (ref "U$4") (pin "5") (pinfunction "GND_5") (pintype "bidirectional"))
      (node (ref "U$4") (pin "DAP") (pinfunction "DAP_DAP") (pintype "bidirectional"))
      (node (ref "U$5") (pin "5") (pinfunction "GND_5") (pintype "bidirectional"))
      (node (ref "U$5") (pin "DAP") (pinfunction "DAP_DAP") (pintype "bidirectional"))
      (node (ref "U$6") (pin "P11.1") (pinfunction "P$5_P11.1") (pintype "bidirectional"))
      (node (ref "U$6") (pin "P11.10") (pinfunction "P$5_P11.10") (pintype "bidirectional"))
      (node (ref "U$6") (pin "P11.2") (pinfunction "P$5_P11.2") (pintype "bidirectional"))
      (node (ref "U$6") (pin "P11.3") (pinfunction "P$5_P11.3") (pintype "bidirectional"))
      (node (ref "U$6") (pin "P11.4") (pinfunction "P$5_P11.4") (pintype "bidirectional"))
      (node (ref "U$6") (pin "P11.5") (pinfunction "P$5_P11.5") (pintype "bidirectional"))
      (node (ref "U$6") (pin "P11.6") (pinfunction "P$5_P11.6") (pintype "bidirectional"))
      (node (ref "U$6") (pin "P11.7") (pinfunction "P$5_P11.7") (pintype "bidirectional"))
      (node (ref "U$6") (pin "P11.8") (pinfunction "P$5_P11.8") (pintype "bidirectional"))
      (node (ref "U$6") (pin "P11.9") (pinfunction "P$5_P11.9") (pintype "bidirectional"))
      (node (ref "U$7") (pin "15") (pinfunction "GND_15") (pintype "bidirectional"))
      (node (ref "U$7") (pin "9") (pinfunction "GND2_9") (pintype "bidirectional"))
      (node (ref "U$8") (pin "15") (pinfunction "GND_15") (pintype "bidirectional"))
      (node (ref "U$8") (pin "9") (pinfunction "GND2_9") (pintype "bidirectional"))
      (node (ref "U1") (pin "5") (pinfunction "GND_5") (pintype "bidirectional"))
      (node (ref "U2") (pin "5") (pinfunction "GND_5") (pintype "bidirectional"))
    )
    (net (code "16") (name "LEDPWM1") (class "Default")
      (node (ref "U$1") (pin "3") (pinfunction "EN_3") (pintype "bidirectional"))
      (node (ref "U$6") (pin "S27") (pinfunction "P$3_S27") (pintype "bidirectional"))
    )
    (net (code "17") (name "LEDPWM2") (class "Default")
      (node (ref "U$2") (pin "3") (pinfunction "EN_3") (pintype "bidirectional"))
      (node (ref "U$6") (pin "S28") (pinfunction "P$4_S28") (pintype "bidirectional"))
    )
    (net (code "18") (name "LEDPWM3") (class "Default")
      (node (ref "U$3") (pin "3") (pinfunction "EN_3") (pintype "bidirectional"))
      (node (ref "U$6") (pin "S29") (pinfunction "P$5_S29") (pintype "bidirectional"))
    )
    (net (code "19") (name "LEDPWM4") (class "Default")
      (node (ref "U$4") (pin "3") (pinfunction "EN_3") (pintype "bidirectional"))
      (node (ref "U$6") (pin "S30") (pinfunction "P$6_S30") (pintype "bidirectional"))
    )
    (net (code "20") (name "LEDPWM5") (class "Default")
      (node (ref "U$5") (pin "3") (pinfunction "EN_3") (pintype "bidirectional"))
      (node (ref "U$6") (pin "S31") (pinfunction "P$7_S31") (pintype "bidirectional"))
    )
    (net (code "21") (name "LEDPWR1") (class "Default")
      (node (ref "L1") (pin "P$2") (pinfunction "2_P$2") (pintype "passive"))
      (node (ref "ROFF") (pin "1") (pinfunction "1_1") (pintype "passive"))
      (node (ref "U$6") (pin "P1.1") (pinfunction "P$1_P1.1") (pintype "bidirectional"))
      (node (ref "U$6") (pin "P1.10") (pinfunction "P$1_P1.10") (pintype "bidirectional"))
      (node (ref "U$6") (pin "P1.2") (pinfunction "P$1_P1.2") (pintype "bidirectional"))
      (node (ref "U$6") (pin "P1.3") (pinfunction "P$1_P1.3") (pintype "bidirectional"))
      (node (ref "U$6") (pin "P1.4") (pinfunction "P$1_P1.4") (pintype "bidirectional"))
      (node (ref "U$6") (pin "P1.5") (pinfunction "P$1_P1.5") (pintype "bidirectional"))
      (node (ref "U$6") (pin "P1.6") (pinfunction "P$1_P1.6") (pintype "bidirectional"))
      (node (ref "U$6") (pin "P1.7") (pinfunction "P$1_P1.7") (pintype "bidirectional"))
      (node (ref "U$6") (pin "P1.8") (pinfunction "P$1_P1.8") (pintype "bidirectional"))
      (node (ref "U$6") (pin "P1.9") (pinfunction "P$1_P1.9") (pintype "bidirectional"))
    )
    (net (code "22") (name "LEDPWR2") (class "Default")
      (node (ref "L2") (pin "P$2") (pinfunction "2_P$2") (pintype "passive"))
      (node (ref "ROFF1") (pin "1") (pinfunction "1_1") (pintype "passive"))
      (node (ref "U$6") (pin "P2.1") (pinfunction "P$2_P2.1") (pintype "bidirectional"))
      (node (ref "U$6") (pin "P2.10") (pinfunction "P$2_P2.10") (pintype "bidirectional"))
      (node (ref "U$6") (pin "P2.2") (pinfunction "P$2_P2.2") (pintype "bidirectional"))
      (node (ref "U$6") (pin "P2.3") (pinfunction "P$2_P2.3") (pintype "bidirectional"))
      (node (ref "U$6") (pin "P2.4") (pinfunction "P$2_P2.4") (pintype "bidirectional"))
      (node (ref "U$6") (pin "P2.5") (pinfunction "P$2_P2.5") (pintype "bidirectional"))
      (node (ref "U$6") (pin "P2.6") (pinfunction "P$2_P2.6") (pintype "bidirectional"))
      (node (ref "U$6") (pin "P2.7") (pinfunction "P$2_P2.7") (pintype "bidirectional"))
      (node (ref "U$6") (pin "P2.8") (pinfunction "P$2_P2.8") (pintype "bidirectional"))
      (node (ref "U$6") (pin "P2.9") (pinfunction "P$2_P2.9") (pintype "bidirectional"))
    )
    (net (code "23") (name "LEDPWR3") (class "Default")
      (node (ref "L3") (pin "P$2") (pinfunction "2_P$2") (pintype "passive"))
      (node (ref "ROFF2") (pin "1") (pinfunction "1_1") (pintype "passive"))
      (node (ref "U$6") (pin "P3.1") (pinfunction "P$3_P3.1") (pintype "bidirectional"))
      (node (ref "U$6") (pin "P3.10") (pinfunction "P$3_P3.10") (pintype "bidirectional"))
      (node (ref "U$6") (pin "P3.2") (pinfunction "P$3_P3.2") (pintype "bidirectional"))
      (node (ref "U$6") (pin "P3.3") (pinfunction "P$3_P3.3") (pintype "bidirectional"))
      (node (ref "U$6") (pin "P3.4") (pinfunction "P$3_P3.4") (pintype "bidirectional"))
      (node (ref "U$6") (pin "P3.5") (pinfunction "P$3_P3.5") (pintype "bidirectional"))
      (node (ref "U$6") (pin "P3.6") (pinfunction "P$3_P3.6") (pintype "bidirectional"))
      (node (ref "U$6") (pin "P3.7") (pinfunction "P$3_P3.7") (pintype "bidirectional"))
      (node (ref "U$6") (pin "P3.8") (pinfunction "P$3_P3.8") (pintype "bidirectional"))
      (node (ref "U$6") (pin "P3.9") (pinfunction "P$3_P3.9") (pintype "bidirectional"))
    )
    (net (code "24") (name "LEDPWR4") (class "Default")
      (node (ref "L4") (pin "P$2") (pinfunction "2_P$2") (pintype "passive"))
      (node (ref "ROFF3") (pin "1") (pinfunction "1_1") (pintype "passive"))
      (node (ref "U$6") (pin "P4.1") (pinfunction "P$4_P4.1") (pintype "bidirectional"))
      (node (ref "U$6") (pin "P4.10") (pinfunction "P$4_P4.10") (pintype "bidirectional"))
      (node (ref "U$6") (pin "P4.2") (pinfunction "P$4_P4.2") (pintype "bidirectional"))
      (node (ref "U$6") (pin "P4.3") (pinfunction "P$4_P4.3") (pintype "bidirectional"))
      (node (ref "U$6") (pin "P4.4") (pinfunction "P$4_P4.4") (pintype "bidirectional"))
      (node (ref "U$6") (pin "P4.5") (pinfunction "P$4_P4.5") (pintype "bidirectional"))
      (node (ref "U$6") (pin "P4.6") (pinfunction "P$4_P4.6") (pintype "bidirectional"))
      (node (ref "U$6") (pin "P4.7") (pinfunction "P$4_P4.7") (pintype "bidirectional"))
      (node (ref "U$6") (pin "P4.8") (pinfunction "P$4_P4.8") (pintype "bidirectional"))
      (node (ref "U$6") (pin "P4.9") (pinfunction "P$4_P4.9") (pintype "bidirectional"))
    )
    (net (code "25") (name "LEDPWR5") (class "Default")
      (node (ref "L5") (pin "P$2") (pinfunction "2_P$2") (pintype "passive"))
      (node (ref "ROFF4") (pin "1") (pinfunction "1_1") (pintype "passive"))
      (node (ref "U$6") (pin "P5.1") (pinfunction "P$5_P5.1") (pintype "bidirectional"))
      (node (ref "U$6") (pin "P5.10") (pinfunction "P$5_P5.10") (pintype "bidirectional"))
      (node (ref "U$6") (pin "P5.2") (pinfunction "P$5_P5.2") (pintype "bidirectional"))
      (node (ref "U$6") (pin "P5.3") (pinfunction "P$5_P5.3") (pintype "bidirectional"))
      (node (ref "U$6") (pin "P5.4") (pinfunction "P$5_P5.4") (pintype "bidirectional"))
      (node (ref "U$6") (pin "P5.5") (pinfunction "P$5_P5.5") (pintype "bidirectional"))
      (node (ref "U$6") (pin "P5.6") (pinfunction "P$5_P5.6") (pintype "bidirectional"))
      (node (ref "U$6") (pin "P5.7") (pinfunction "P$5_P5.7") (pintype "bidirectional"))
      (node (ref "U$6") (pin "P5.8") (pinfunction "P$5_P5.8") (pintype "bidirectional"))
      (node (ref "U$6") (pin "P5.9") (pinfunction "P$5_P5.9") (pintype "bidirectional"))
    )
    (net (code "26") (name "LKJOI") (class "Default")
      (node (ref "ACS1") (pin "1") (pinfunction "IP+_1") (pintype "bidirectional"))
      (node (ref "ACS1") (pin "2") (pinfunction "IP+1_2") (pintype "bidirectional"))
      (node (ref "U$12") (pin "8") (pinfunction "OUT2_8") (pintype "bidirectional"))
    )
    (net (code "27") (name "N$46") (class "Default")
      (node (ref "U$6") (pin "S1") (pinfunction "P$1_S1") (pintype "bidirectional"))
    )
    (net (code "28") (name "N$47") (class "Default")
      (node (ref "U$6") (pin "S2") (pinfunction "P$2_S2") (pintype "bidirectional"))
    )
    (net (code "29") (name "N$48") (class "Default")
      (node (ref "U$6") (pin "S3") (pinfunction "P$3_S3") (pintype "bidirectional"))
    )
    (net (code "30") (name "N$49") (class "Default")
      (node (ref "U$6") (pin "S4") (pinfunction "P$4_S4") (pintype "bidirectional"))
    )
    (net (code "31") (name "N$50") (class "Default")
      (node (ref "U$6") (pin "S5") (pinfunction "P$5_S5") (pintype "bidirectional"))
    )
    (net (code "32") (name "N$68") (class "Default")
      (node (ref "U$6") (pin "S23") (pinfunction "P$7_S23") (pintype "bidirectional"))
    )
    (net (code "33") (name "N$69") (class "Default")
      (node (ref "U$6") (pin "S24") (pinfunction "P$8_S24") (pintype "bidirectional"))
    )
    (net (code "34") (name "N$90") (class "Default")
      (node (ref "U$6") (pin "S45") (pinfunction "P$5_S45") (pintype "bidirectional"))
    )
    (net (code "35") (name "N$91") (class "Default")
      (node (ref "U$6") (pin "S46") (pinfunction "P$6_S46") (pintype "bidirectional"))
    )
    (net (code "36") (name "Net-(ACS1-~{FAULT})") (class "Default")
      (node (ref "ACS1") (pin "6") (pinfunction "~{FAULT}_6") (pintype "bidirectional"))
      (node (ref "R12") (pin "2") (pinfunction "2_2") (pintype "passive"))
    )
    (net (code "37") (name "Net-(ACS711-~{FAULT})") (class "Default")
      (node (ref "ACS711") (pin "6") (pinfunction "~{FAULT}_6") (pintype "bidirectional"))
      (node (ref "R10") (pin "2") (pinfunction "2_2") (pintype "passive"))
    )
    (net (code "38") (name "Net-(L1-1)") (class "Default")
      (node (ref "D1") (pin "C") (pinfunction "C_C") (pintype "passive"))
      (node (ref "L1") (pin "P$1") (pinfunction "1_P$1") (pintype "passive"))
      (node (ref "Q1") (pin "3") (pinfunction "D_3") (pintype "passive"))
    )
    (net (code "39") (name "Net-(L2-1)") (class "Default")
      (node (ref "D2") (pin "C") (pinfunction "C_C") (pintype "passive"))
      (node (ref "L2") (pin "P$1") (pinfunction "1_P$1") (pintype "passive"))
      (node (ref "Q2") (pin "3") (pinfunction "D_3") (pintype "passive"))
    )
    (net (code "40") (name "Net-(L3-1)") (class "Default")
      (node (ref "D3") (pin "C") (pinfunction "C_C") (pintype "passive"))
      (node (ref "L3") (pin "P$1") (pinfunction "1_P$1") (pintype "passive"))
      (node (ref "Q3") (pin "3") (pinfunction "D_3") (pintype "passive"))
    )
    (net (code "41") (name "Net-(L4-1)") (class "Default")
      (node (ref "D4") (pin "C") (pinfunction "C_C") (pintype "passive"))
      (node (ref "L4") (pin "P$1") (pinfunction "1_P$1") (pintype "passive"))
      (node (ref "Q4") (pin "3") (pinfunction "D_3") (pintype "passive"))
    )
    (net (code "42") (name "Net-(L5-1)") (class "Default")
      (node (ref "D5") (pin "C") (pinfunction "C_C") (pintype "passive"))
      (node (ref "L5") (pin "P$1") (pinfunction "1_P$1") (pintype "passive"))
      (node (ref "Q5") (pin "3") (pinfunction "D_3") (pintype "passive"))
    )
    (net (code "43") (name "Net-(OK1A-A)") (class "Default")
      (node (ref "OK1") (pin "1") (pinfunction "A_1") (pintype "passive"))
      (node (ref "R1") (pin "2") (pinfunction "2_2") (pintype "passive"))
    )
    (net (code "44") (name "Net-(OK1A-C)") (class "Default")
      (node (ref "C1") (pin "2") (pinfunction "2_2") (pintype "passive"))
      (node (ref "C2") (pin "1") (pinfunction "1_1") (pintype "passive"))
      (node (ref "C3") (pin "1") (pinfunction "1_1") (pintype "passive"))
      (node (ref "OK1") (pin "2") (pinfunction "C_2") (pintype "passive"))
      (node (ref "OK1") (pin "4") (pinfunction "C_4") (pintype "passive"))
      (node (ref "OK1") (pin "6") (pinfunction "C_6") (pintype "passive"))
      (node (ref "U$10") (pin "A") (pinfunction "A_A") (pintype "passive"))
    )
    (net (code "45") (name "Net-(OK1B-A)") (class "Default")
      (node (ref "OK1") (pin "3") (pinfunction "A_3") (pintype "passive"))
      (node (ref "R2") (pin "2") (pinfunction "2_2") (pintype "passive"))
    )
    (net (code "46") (name "Net-(OK1C-A)") (class "Default")
      (node (ref "OK1") (pin "5") (pinfunction "A_5") (pintype "passive"))
      (node (ref "R3") (pin "2") (pinfunction "2_2") (pintype "passive"))
    )
    (net (code "47") (name "Net-(Q1-G)") (class "Default")
      (node (ref "Q1") (pin "1") (pinfunction "G_1") (pintype "passive"))
      (node (ref "U$1") (pin "6") (pinfunction "PGATE_6") (pintype "bidirectional"))
    )
    (net (code "48") (name "Net-(Q1-S)") (class "Default")
      (node (ref "Q1") (pin "2") (pinfunction "S_2") (pintype "passive"))
      (node (ref "RSNS") (pin "2") (pinfunction "2_2") (pintype "passive"))
      (node (ref "U$1") (pin "7") (pinfunction "CSN_7") (pintype "bidirectional"))
    )
    (net (code "49") (name "Net-(Q2-G)") (class "Default")
      (node (ref "Q2") (pin "1") (pinfunction "G_1") (pintype "passive"))
      (node (ref "U$2") (pin "6") (pinfunction "PGATE_6") (pintype "bidirectional"))
    )
    (net (code "50") (name "Net-(Q2-S)") (class "Default")
      (node (ref "Q2") (pin "2") (pinfunction "S_2") (pintype "passive"))
      (node (ref "RSNS1") (pin "2") (pinfunction "2_2") (pintype "passive"))
      (node (ref "U$2") (pin "7") (pinfunction "CSN_7") (pintype "bidirectional"))
    )
    (net (code "51") (name "Net-(Q3-G)") (class "Default")
      (node (ref "Q3") (pin "1") (pinfunction "G_1") (pintype "passive"))
      (node (ref "U$3") (pin "6") (pinfunction "PGATE_6") (pintype "bidirectional"))
    )
    (net (code "52") (name "Net-(Q3-S)") (class "Default")
      (node (ref "Q3") (pin "2") (pinfunction "S_2") (pintype "passive"))
      (node (ref "RSNS2") (pin "2") (pinfunction "2_2") (pintype "passive"))
      (node (ref "U$3") (pin "7") (pinfunction "CSN_7") (pintype "bidirectional"))
    )
    (net (code "53") (name "Net-(Q4-G)") (class "Default")
      (node (ref "Q4") (pin "1") (pinfunction "G_1") (pintype "passive"))
      (node (ref "U$4") (pin "6") (pinfunction "PGATE_6") (pintype "bidirectional"))
    )
    (net (code "54") (name "Net-(Q4-S)") (class "Default")
      (node (ref "Q4") (pin "2") (pinfunction "S_2") (pintype "passive"))
      (node (ref "RSNS3") (pin "2") (pinfunction "2_2") (pintype "passive"))
      (node (ref "U$4") (pin "7") (pinfunction "CSN_7") (pintype "bidirectional"))
    )
    (net (code "55") (name "Net-(Q5-G)") (class "Default")
      (node (ref "Q5") (pin "1") (pinfunction "G_1") (pintype "passive"))
      (node (ref "U$5") (pin "6") (pinfunction "PGATE_6") (pintype "bidirectional"))
    )
    (net (code "56") (name "Net-(Q5-S)") (class "Default")
      (node (ref "Q5") (pin "2") (pinfunction "S_2") (pintype "passive"))
      (node (ref "RSNS4") (pin "2") (pinfunction "2_2") (pintype "passive"))
      (node (ref "U$5") (pin "7") (pinfunction "CSN_7") (pintype "bidirectional"))
    )
    (net (code "57") (name "Net-(U$1-COFF)") (class "Default")
      (node (ref "COFF") (pin "1") (pinfunction "1_1") (pintype "passive"))
      (node (ref "ROFF") (pin "2") (pinfunction "2_2") (pintype "passive"))
      (node (ref "U$1") (pin "4") (pinfunction "COFF_4") (pintype "bidirectional"))
    )
    (net (code "58") (name "Net-(U$1-UVLO)") (class "Default")
      (node (ref "RUV1") (pin "2") (pinfunction "2_2") (pintype "passive"))
      (node (ref "RUV2") (pin "1") (pinfunction "1_1") (pintype "passive"))
      (node (ref "U$1") (pin "1") (pinfunction "UVLO_1") (pintype "bidirectional"))
    )
    (net (code "59") (name "Net-(U$1-VCC)") (class "Default")
      (node (ref "CF") (pin "2") (pinfunction "2_2") (pintype "passive"))
      (node (ref "U$1") (pin "9") (pinfunction "VCC_9") (pintype "bidirectional"))
    )
    (net (code "60") (name "Net-(U$2-COFF)") (class "Default")
      (node (ref "COFF1") (pin "1") (pinfunction "1_1") (pintype "passive"))
      (node (ref "ROFF1") (pin "2") (pinfunction "2_2") (pintype "passive"))
      (node (ref "U$2") (pin "4") (pinfunction "COFF_4") (pintype "bidirectional"))
    )
    (net (code "61") (name "Net-(U$2-UVLO)") (class "Default")
      (node (ref "RUV3") (pin "2") (pinfunction "2_2") (pintype "passive"))
      (node (ref "RUV4") (pin "1") (pinfunction "1_1") (pintype "passive"))
      (node (ref "U$2") (pin "1") (pinfunction "UVLO_1") (pintype "bidirectional"))
    )
    (net (code "62") (name "Net-(U$2-VCC)") (class "Default")
      (node (ref "CF1") (pin "2") (pinfunction "2_2") (pintype "passive"))
      (node (ref "U$2") (pin "9") (pinfunction "VCC_9") (pintype "bidirectional"))
    )
    (net (code "63") (name "Net-(U$3-COFF)") (class "Default")
      (node (ref "COFF2") (pin "1") (pinfunction "1_1") (pintype "passive"))
      (node (ref "ROFF2") (pin "2") (pinfunction "2_2") (pintype "passive"))
      (node (ref "U$3") (pin "4") (pinfunction "COFF_4") (pintype "bidirectional"))
    )
    (net (code "64") (name "Net-(U$3-UVLO)") (class "Default")
      (node (ref "RUV5") (pin "2") (pinfunction "2_2") (pintype "passive"))
      (node (ref "RUV6") (pin "1") (pinfunction "1_1") (pintype "passive"))
      (node (ref "U$3") (pin "1") (pinfunction "UVLO_1") (pintype "bidirectional"))
    )
    (net (code "65") (name "Net-(U$3-VCC)") (class "Default")
      (node (ref "CF2") (pin "2") (pinfunction "2_2") (pintype "passive"))
      (node (ref "U$3") (pin "9") (pinfunction "VCC_9") (pintype "bidirectional"))
    )
    (net (code "66") (name "Net-(U$4-COFF)") (class "Default")
      (node (ref "COFF3") (pin "1") (pinfunction "1_1") (pintype "passive"))
      (node (ref "ROFF3") (pin "2") (pinfunction "2_2") (pintype "passive"))
      (node (ref "U$4") (pin "4") (pinfunction "COFF_4") (pintype "bidirectional"))
    )
    (net (code "67") (name "Net-(U$4-UVLO)") (class "Default")
      (node (ref "RUV7") (pin "2") (pinfunction "2_2") (pintype "passive"))
      (node (ref "RUV8") (pin "1") (pinfunction "1_1") (pintype "passive"))
      (node (ref "U$4") (pin "1") (pinfunction "UVLO_1") (pintype "bidirectional"))
    )
    (net (code "68") (name "Net-(U$4-VCC)") (class "Default")
      (node (ref "CF3") (pin "2") (pinfunction "2_2") (pintype "passive"))
      (node (ref "U$4") (pin "9") (pinfunction "VCC_9") (pintype "bidirectional"))
    )
    (net (code "69") (name "Net-(U$5-COFF)") (class "Default")
      (node (ref "COFF4") (pin "1") (pinfunction "1_1") (pintype "passive"))
      (node (ref "ROFF4") (pin "2") (pinfunction "2_2") (pintype "passive"))
      (node (ref "U$5") (pin "4") (pinfunction "COFF_4") (pintype "bidirectional"))
    )
    (net (code "70") (name "Net-(U$5-UVLO)") (class "Default")
      (node (ref "RUV10") (pin "1") (pinfunction "1_1") (pintype "passive"))
      (node (ref "RUV9") (pin "2") (pinfunction "2_2") (pintype "passive"))
      (node (ref "U$5") (pin "1") (pinfunction "UVLO_1") (pintype "bidirectional"))
    )
    (net (code "71") (name "Net-(U$5-VCC)") (class "Default")
      (node (ref "CF4") (pin "2") (pinfunction "2_2") (pintype "passive"))
      (node (ref "U$5") (pin "9") (pinfunction "VCC_9") (pintype "bidirectional"))
    )
    (net (code "72") (name "Net-(U$7-MS1)") (class "Default")
      (node (ref "R13") (pin "2") (pinfunction "2_2") (pintype "passive"))
      (node (ref "U$7") (pin "2") (pinfunction "MS1_2") (pintype "bidirectional"))
      (node (ref "U$7") (pin "3") (pinfunction "MS2_3") (pintype "bidirectional"))
      (node (ref "U$7") (pin "4") (pinfunction "MS3_4") (pintype "bidirectional"))
    )
    (net (code "73") (name "Net-(U$7-~{RST})") (class "Default")
      (node (ref "U$7") (pin "5") (pinfunction "~{RST}_5") (pintype "bidirectional"))
      (node (ref "U$7") (pin "6") (pinfunction "~{SLP}_6") (pintype "bidirectional"))
    )
    (net (code "74") (name "Net-(U$8-MS1)") (class "Default")
      (node (ref "R14") (pin "2") (pinfunction "2_2") (pintype "passive"))
      (node (ref "U$8") (pin "2") (pinfunction "MS1_2") (pintype "bidirectional"))
      (node (ref "U$8") (pin "3") (pinfunction "MS2_3") (pintype "bidirectional"))
      (node (ref "U$8") (pin "4") (pinfunction "MS3_4") (pintype "bidirectional"))
    )
    (net (code "75") (name "Net-(U$8-~{RST})") (class "Default")
      (node (ref "U$8") (pin "5") (pinfunction "~{RST}_5") (pintype "bidirectional"))
      (node (ref "U$8") (pin "6") (pinfunction "~{SLP}_6") (pintype "bidirectional"))
    )
    (net (code "76") (name "Net-(U$11-LSS)") (class "Default")
      (node (ref "R9") (pin "2") (pinfunction "2_2") (pintype "passive"))
      (node (ref "U$11") (pin "7") (pinfunction "LSS_7") (pintype "bidirectional"))
    )
    (net (code "77") (name "Net-(U$12-LSS)") (class "Default")
      (node (ref "R11") (pin "2") (pinfunction "2_2") (pintype "passive"))
      (node (ref "U$12") (pin "7") (pinfunction "LSS_7") (pintype "bidirectional"))
    )
    (net (code "78") (name "Net-(U1-~{FAULT})") (class "Default")
      (node (ref "R8") (pin "1") (pinfunction "1_1") (pintype "passive"))
      (node (ref "U1") (pin "6") (pinfunction "~{FAULT}_6") (pintype "bidirectional"))
    )
    (net (code "79") (name "Net-(U2-~{FAULT})") (class "Default")
      (node (ref "R7") (pin "1") (pinfunction "1_1") (pintype "passive"))
      (node (ref "U2") (pin "6") (pinfunction "~{FAULT}_6") (pintype "bidirectional"))
    )
    (net (code "80") (name "SERVO1CURRENT") (class "Default")
      (node (ref "C7") (pin "1") (pinfunction "1_1") (pintype "passive"))
      (node (ref "U$6") (pin "S36") (pinfunction "P$4_S36") (pintype "bidirectional"))
      (node (ref "U2") (pin "7") (pinfunction "VIOUT_7") (pintype "bidirectional"))
    )
    (net (code "81") (name "SERVO2CURRENT") (class "Default")
      (node (ref "C6") (pin "1") (pinfunction "1_1") (pintype "passive"))
      (node (ref "U$6") (pin "S35") (pinfunction "P$3_S35") (pintype "bidirectional"))
      (node (ref "U1") (pin "7") (pinfunction "VIOUT_7") (pintype "bidirectional"))
    )
    (net (code "82") (name "STEP1") (class "Default")
      (node (ref "U$6") (pin "S33") (pinfunction "P$1_S33") (pintype "bidirectional"))
      (node (ref "U$7") (pin "7") (pinfunction "STEP_7") (pintype "bidirectional"))
    )
    (net (code "83") (name "STEP1A1") (class "Default")
      (node (ref "U$6") (pin "S13") (pinfunction "P$5_S13") (pintype "bidirectional"))
      (node (ref "U$7") (pin "12") (pinfunction "1A_12") (pintype "bidirectional"))
    )
    (net (code "84") (name "STEP1A2") (class "Default")
      (node (ref "U$6") (pin "S14") (pinfunction "P$6_S14") (pintype "bidirectional"))
      (node (ref "U$7") (pin "13") (pinfunction "2A_13") (pintype "bidirectional"))
    )
    (net (code "85") (name "STEP1B1") (class "Default")
      (node (ref "U$6") (pin "S15") (pinfunction "P$7_S15") (pintype "bidirectional"))
      (node (ref "U$7") (pin "11") (pinfunction "1B_11") (pintype "bidirectional"))
    )
    (net (code "86") (name "STEP1B2") (class "Default")
      (node (ref "U$6") (pin "S16") (pinfunction "P$8_S16") (pintype "bidirectional"))
      (node (ref "U$7") (pin "14") (pinfunction "2B_14") (pintype "bidirectional"))
    )
    (net (code "87") (name "STEP2") (class "Default")
      (node (ref "U$6") (pin "S43") (pinfunction "P$3_S43") (pintype "bidirectional"))
      (node (ref "U$8") (pin "7") (pinfunction "STEP_7") (pintype "bidirectional"))
    )
    (net (code "88") (name "STEP2A1") (class "Default")
      (node (ref "U$6") (pin "S9") (pinfunction "P$1_S9") (pintype "bidirectional"))
      (node (ref "U$8") (pin "12") (pinfunction "1A_12") (pintype "bidirectional"))
    )
    (net (code "89") (name "STEP2A2") (class "Default")
      (node (ref "U$6") (pin "S10") (pinfunction "P$2_S10") (pintype "bidirectional"))
      (node (ref "U$8") (pin "13") (pinfunction "2A_13") (pintype "bidirectional"))
    )
    (net (code "90") (name "STEP2B1") (class "Default")
      (node (ref "U$6") (pin "S11") (pinfunction "P$3_S11") (pintype "bidirectional"))
      (node (ref "U$8") (pin "11") (pinfunction "1B_11") (pintype "bidirectional"))
    )
    (net (code "91") (name "STEP2B2") (class "Default")
      (node (ref "U$6") (pin "S12") (pinfunction "P$4_S12") (pintype "bidirectional"))
      (node (ref "U$8") (pin "14") (pinfunction "2B_14") (pintype "bidirectional"))
    )
    (net (code "92") (name "STEPDIR1") (class "Default")
      (node (ref "U$6") (pin "S44") (pinfunction "P$4_S44") (pintype "bidirectional"))
      (node (ref "U$7") (pin "8") (pinfunction "DIR_8") (pintype "bidirectional"))
    )
    (net (code "93") (name "STEPDIR2") (class "Default")
      (node (ref "U$6") (pin "S42") (pinfunction "P$2_S42") (pintype "bidirectional"))
      (node (ref "U$8") (pin "8") (pinfunction "DIR_8") (pintype "bidirectional"))
    )
    (net (code "94") (name "STEPEN") (class "Default")
      (node (ref "U$6") (pin "S34") (pinfunction "P$2_S34") (pintype "bidirectional"))
      (node (ref "U$7") (pin "1") (pinfunction "~{EN}_1") (pintype "bidirectional"))
      (node (ref "U$8") (pin "1") (pinfunction "~{EN}_1") (pintype "bidirectional"))
    )
    (net (code "95") (name "TURN+") (class "Default")
      (node (ref "U$12") (pin "6") (pinfunction "OUT1_6") (pintype "bidirectional"))
      (node (ref "U$6") (pin "P8.1") (pinfunction "P$2_P8.1") (pintype "bidirectional"))
      (node (ref "U$6") (pin "P8.10") (pinfunction "P$2_P8.10") (pintype "bidirectional"))
      (node (ref "U$6") (pin "P8.2") (pinfunction "P$2_P8.2") (pintype "bidirectional"))
      (node (ref "U$6") (pin "P8.3") (pinfunction "P$2_P8.3") (pintype "bidirectional"))
      (node (ref "U$6") (pin "P8.4") (pinfunction "P$2_P8.4") (pintype "bidirectional"))
      (node (ref "U$6") (pin "P8.5") (pinfunction "P$2_P8.5") (pintype "bidirectional"))
      (node (ref "U$6") (pin "P8.6") (pinfunction "P$2_P8.6") (pintype "bidirectional"))
      (node (ref "U$6") (pin "P8.7") (pinfunction "P$2_P8.7") (pintype "bidirectional"))
      (node (ref "U$6") (pin "P8.8") (pinfunction "P$2_P8.8") (pintype "bidirectional"))
      (node (ref "U$6") (pin "P8.9") (pinfunction "P$2_P8.9") (pintype "bidirectional"))
    )
    (net (code "96") (name "TURN-") (class "Default")
      (node (ref "ACS1") (pin "3") (pinfunction "IP-_3") (pintype "bidirectional"))
      (node (ref "ACS1") (pin "4") (pinfunction "IP-1_4") (pintype "bidirectional"))
      (node (ref "U$6") (pin "P9.1") (pinfunction "P$3_P9.1") (pintype "bidirectional"))
      (node (ref "U$6") (pin "P9.10") (pinfunction "P$3_P9.10") (pintype "bidirectional"))
      (node (ref "U$6") (pin "P9.2") (pinfunction "P$3_P9.2") (pintype "bidirectional"))
      (node (ref "U$6") (pin "P9.3") (pinfunction "P$3_P9.3") (pintype "bidirectional"))
      (node (ref "U$6") (pin "P9.4") (pinfunction "P$3_P9.4") (pintype "bidirectional"))
      (node (ref "U$6") (pin "P9.5") (pinfunction "P$3_P9.5") (pintype "bidirectional"))
      (node (ref "U$6") (pin "P9.6") (pinfunction "P$3_P9.6") (pintype "bidirectional"))
      (node (ref "U$6") (pin "P9.7") (pinfunction "P$3_P9.7") (pintype "bidirectional"))
      (node (ref "U$6") (pin "P9.8") (pinfunction "P$3_P9.8") (pintype "bidirectional"))
      (node (ref "U$6") (pin "P9.9") (pinfunction "P$3_P9.9") (pintype "bidirectional"))
    )
    (net (code "97") (name "TURNCURRENT") (class "Default")
      (node (ref "ACS1") (pin "7") (pinfunction "VIOUT_7") (pintype "bidirectional"))
      (node (ref "U$6") (pin "S37") (pinfunction "P$5_S37") (pintype "bidirectional"))
    )
    (net (code "98") (name "TURNPWM1") (class "Default")
      (node (ref "U$12") (pin "3") (pinfunction "IN1_3") (pintype "bidirectional"))
      (node (ref "U$6") (pin "S39") (pinfunction "P$7_S39") (pintype "bidirectional"))
    )
    (net (code "99") (name "TURNPWM2") (class "Default")
      (node (ref "U$12") (pin "2") (pinfunction "IN2_2") (pintype "bidirectional"))
      (node (ref "U$6") (pin "S38") (pinfunction "P$6_S38") (pintype "bidirectional"))
    )
    (net (code "100") (name "VPROBE1") (class "Default")
      (node (ref "C1") (pin "1") (pinfunction "1_1") (pintype "passive"))
      (node (ref "R1") (pin "1") (pinfunction "1_1") (pintype "passive"))
      (node (ref "U$6") (pin "S19") (pinfunction "P$3_S19") (pintype "bidirectional"))
    )
    (net (code "101") (name "VPROBE2") (class "Default")
      (node (ref "C2") (pin "2") (pinfunction "2_2") (pintype "passive"))
      (node (ref "R2") (pin "1") (pinfunction "1_1") (pintype "passive"))
      (node (ref "U$6") (pin "S18") (pinfunction "P$2_S18") (pintype "bidirectional"))
    )
    (net (code "102") (name "VPROBE3") (class "Default")
      (node (ref "C3") (pin "2") (pinfunction "2_2") (pintype "passive"))
      (node (ref "R3") (pin "1") (pinfunction "1_1") (pintype "passive"))
      (node (ref "U$6") (pin "S17") (pinfunction "P$1_S17") (pintype "bidirectional"))
    )
    (net (code "103") (name "VSEN1") (class "Default")
      (node (ref "OK1") (pin "16") (pinfunction "COL_16") (pintype "passive"))
      (node (ref "R4") (pin "1") (pinfunction "1_1") (pintype "passive"))
      (node (ref "U$6") (pin "S8") (pinfunction "P$8_S8") (pintype "bidirectional"))
    )
    (net (code "104") (name "VSEN2") (class "Default")
      (node (ref "OK1") (pin "14") (pinfunction "COL_14") (pintype "passive"))
      (node (ref "R5") (pin "1") (pinfunction "1_1") (pintype "passive"))
      (node (ref "U$6") (pin "S7") (pinfunction "P$7_S7") (pintype "bidirectional"))
    )
    (net (code "105") (name "VSEN3") (class "Default")
      (node (ref "OK1") (pin "12") (pinfunction "COL_12") (pintype "passive"))
      (node (ref "R6") (pin "1") (pinfunction "1_1") (pintype "passive"))
      (node (ref "U$6") (pin "S6") (pinfunction "P$6_S6") (pintype "bidirectional"))
    )
    (net (code "106") (name "WEFSFE") (class "Default")
      (node (ref "ACS711") (pin "1") (pinfunction "IP+_1") (pintype "bidirectional"))
      (node (ref "ACS711") (pin "2") (pinfunction "IP+1_2") (pintype "bidirectional"))
      (node (ref "U$11") (pin "8") (pinfunction "OUT2_8") (pintype "bidirectional"))
    )
    (net (code "107") (name "unconnected-(U$1-IADJ-Pad2)") (class "Default")
      (node (ref "U$1") (pin "2") (pinfunction "IADJ_2") (pintype "bidirectional"))
    )
    (net (code "108") (name "unconnected-(U$2-IADJ-Pad2)") (class "Default")
      (node (ref "U$2") (pin "2") (pinfunction "IADJ_2") (pintype "bidirectional"))
    )
    (net (code "109") (name "unconnected-(U$3-IADJ-Pad2)") (class "Default")
      (node (ref "U$3") (pin "2") (pinfunction "IADJ_2") (pintype "bidirectional"))
    )
    (net (code "110") (name "unconnected-(U$4-IADJ-Pad2)") (class "Default")
      (node (ref "U$4") (pin "2") (pinfunction "IADJ_2") (pintype "bidirectional"))
    )
    (net (code "111") (name "unconnected-(U$5-IADJ-Pad2)") (class "Default")
      (node (ref "U$5") (pin "2") (pinfunction "IADJ_2") (pintype "bidirectional"))
    )
  )
)
